# 8x8x8_LED_Cube.net
KiCad netlist of a schematic drawn in Altium Designer
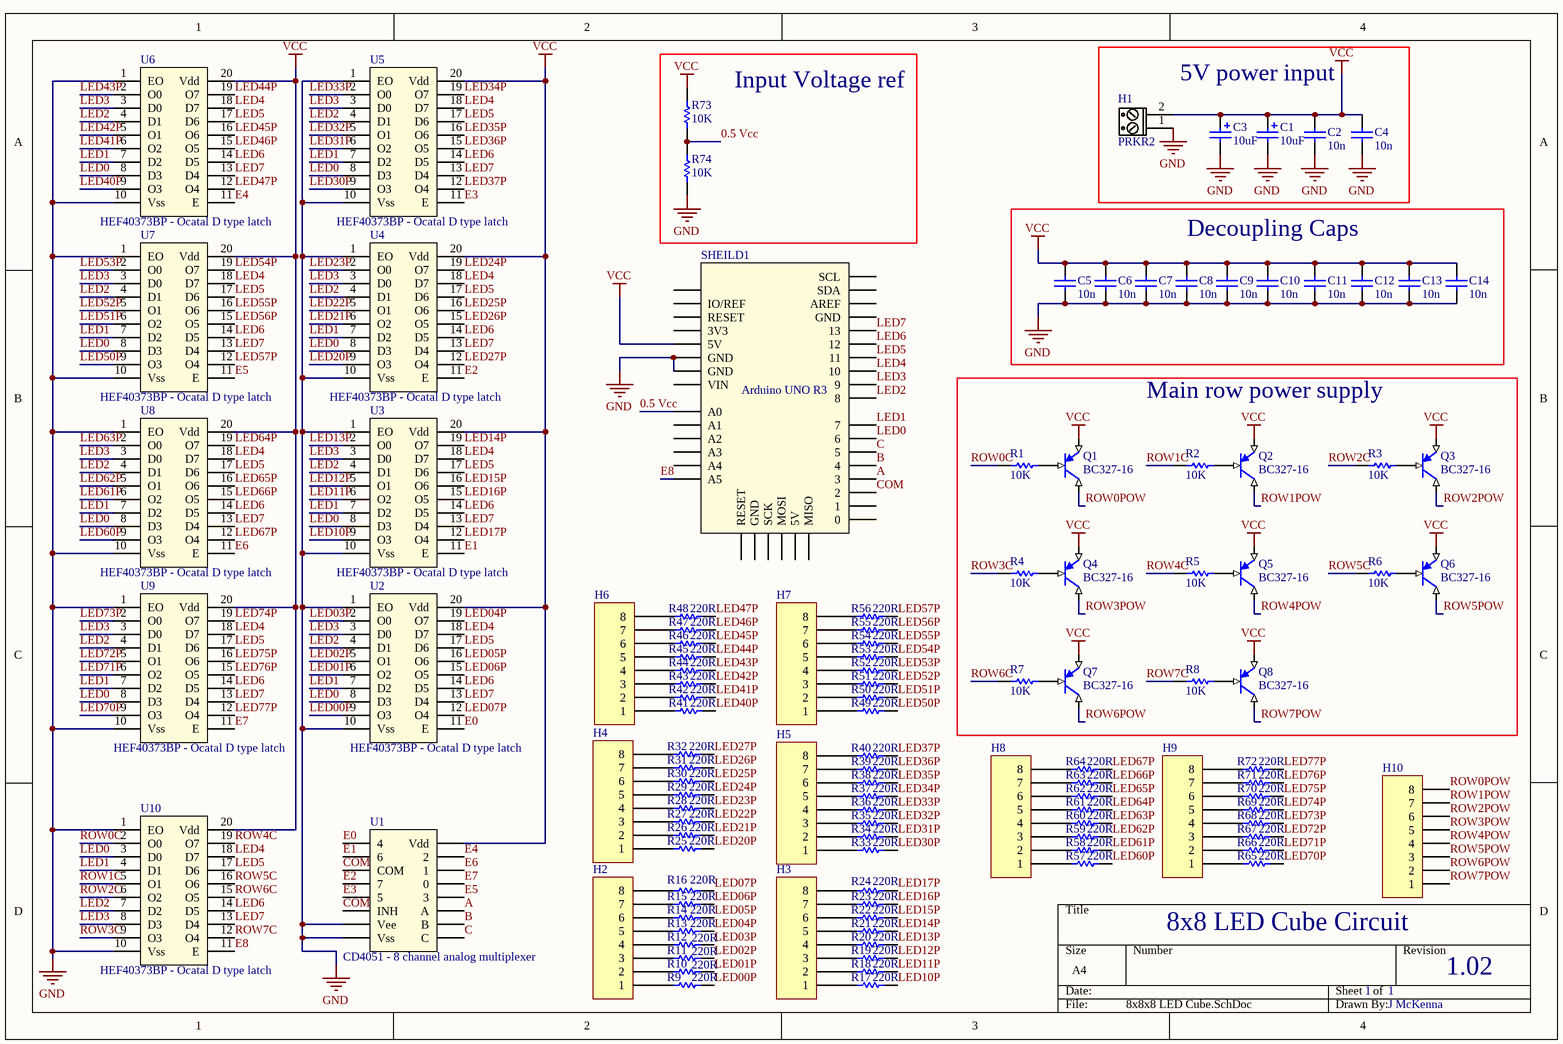
[diagram p0: 8x8x8 LED Cube.SchDoc]

(export (version "E")
  (design (tool "Eeschema 10.0.6"))
  (components
    (comp (ref "C1")
      (value "10uF")
      (footprint "RB.15/.3")
      (description "Polarized Capacitor (Radial)")
      (fields
        (field (name "MANUFACTURER") "Generic Components")
        (field (name "Comment") "Cap Pol1")
        (field (name "PUBLISHER") "Altium Hobart Technology Centre")
      )
      (libsource (lib "MasseyLibs") (part "Cap Pol1"))
    )
    (comp (ref "C2")
      (value "10n")
      (footprint "RAD300")
      (description "Capacitor")
      (fields
        (field (name "MANUFACTURER") "Generic Components")
        (field (name "Comment") "Cap")
        (field (name "PUBLISHER") "Altium Hobart Technology Centre")
      )
      (libsource (lib "MasseyLibs") (part "Cap"))
    )
    (comp (ref "C3")
      (value "10uF")
      (footprint "RB.15/.3")
      (description "Polarized Capacitor (Radial)")
      (fields
        (field (name "MANUFACTURER") "Generic Components")
        (field (name "Comment") "Cap Pol1")
        (field (name "PUBLISHER") "Altium Hobart Technology Centre")
      )
      (libsource (lib "MasseyLibs") (part "Cap Pol1"))
    )
    (comp (ref "C4")
      (value "10n")
      (footprint "RAD300")
      (description "Capacitor")
      (fields
        (field (name "MANUFACTURER") "Generic Components")
        (field (name "Comment") "Cap")
        (field (name "PUBLISHER") "Altium Hobart Technology Centre")
      )
      (libsource (lib "MasseyLibs") (part "Cap"))
    )
    (comp (ref "C5")
      (value "10n")
      (footprint "RAD200_A")
      (description "Capacitor")
      (fields
        (field (name "MANUFACTURER") "Generic Components")
        (field (name "Comment") "Cap")
        (field (name "PUBLISHER") "Altium Hobart Technology Centre")
      )
      (libsource (lib "MasseyLibs") (part "Cap"))
    )
    (comp (ref "C6")
      (value "10n")
      (footprint "RAD200_A")
      (description "Capacitor")
      (fields
        (field (name "MANUFACTURER") "Generic Components")
        (field (name "Comment") "Cap")
        (field (name "PUBLISHER") "Altium Hobart Technology Centre")
      )
      (libsource (lib "MasseyLibs") (part "Cap"))
    )
    (comp (ref "C7")
      (value "10n")
      (footprint "RAD200_A")
      (description "Capacitor")
      (fields
        (field (name "MANUFACTURER") "Generic Components")
        (field (name "Comment") "Cap")
        (field (name "PUBLISHER") "Altium Hobart Technology Centre")
      )
      (libsource (lib "MasseyLibs") (part "Cap"))
    )
    (comp (ref "C8")
      (value "10n")
      (footprint "RAD200_A")
      (description "Capacitor")
      (fields
        (field (name "MANUFACTURER") "Generic Components")
        (field (name "Comment") "Cap")
        (field (name "PUBLISHER") "Altium Hobart Technology Centre")
      )
      (libsource (lib "MasseyLibs") (part "Cap"))
    )
    (comp (ref "C9")
      (value "10n")
      (footprint "RAD200_A")
      (description "Capacitor")
      (fields
        (field (name "MANUFACTURER") "Generic Components")
        (field (name "Comment") "Cap")
        (field (name "PUBLISHER") "Altium Hobart Technology Centre")
      )
      (libsource (lib "MasseyLibs") (part "Cap"))
    )
    (comp (ref "C10")
      (value "10n")
      (footprint "RAD200_A")
      (description "Capacitor")
      (fields
        (field (name "MANUFACTURER") "Generic Components")
        (field (name "Comment") "Cap")
        (field (name "PUBLISHER") "Altium Hobart Technology Centre")
      )
      (libsource (lib "MasseyLibs") (part "Cap"))
    )
    (comp (ref "C11")
      (value "10n")
      (footprint "RAD200_A")
      (description "Capacitor")
      (fields
        (field (name "MANUFACTURER") "Generic Components")
        (field (name "Comment") "Cap")
        (field (name "PUBLISHER") "Altium Hobart Technology Centre")
      )
      (libsource (lib "MasseyLibs") (part "Cap"))
    )
    (comp (ref "C12")
      (value "10n")
      (footprint "RAD200_A")
      (description "Capacitor")
      (fields
        (field (name "MANUFACTURER") "Generic Components")
        (field (name "Comment") "Cap")
        (field (name "PUBLISHER") "Altium Hobart Technology Centre")
      )
      (libsource (lib "MasseyLibs") (part "Cap"))
    )
    (comp (ref "C13")
      (value "10n")
      (footprint "RAD200_A")
      (description "Capacitor")
      (fields
        (field (name "MANUFACTURER") "Generic Components")
        (field (name "Comment") "Cap")
        (field (name "PUBLISHER") "Altium Hobart Technology Centre")
      )
      (libsource (lib "MasseyLibs") (part "Cap"))
    )
    (comp (ref "C14")
      (value "10n")
      (footprint "RAD200_A")
      (description "Capacitor")
      (fields
        (field (name "MANUFACTURER") "Generic Components")
        (field (name "Comment") "Cap")
        (field (name "PUBLISHER") "Altium Hobart Technology Centre")
      )
      (libsource (lib "MasseyLibs") (part "Cap"))
    )
    (comp (ref "H1")
      (value "PRKR2")
      (footprint "PRKR2")
      (description "SCREW TERMINAL 5MM")
      (libsource (lib "vh_altium_library") (part "PRKR2"))
    )
    (comp (ref "H2")
      (value "Header 98")
      (footprint "HDR1X8")
      (description "Header, 8-Pin")
      (fields (field (name "MANUFACTURER") "Generic Components"))
      (libsource (lib "MasseyLibs") (part "Header 8"))
    )
    (comp (ref "H3")
      (value "Header 98")
      (footprint "HDR1X8")
      (description "Header, 8-Pin")
      (fields (field (name "MANUFACTURER") "Generic Components"))
      (libsource (lib "MasseyLibs") (part "Header 8"))
    )
    (comp (ref "H4")
      (value "Header 98")
      (footprint "HDR1X8")
      (description "Header, 8-Pin")
      (fields (field (name "MANUFACTURER") "Generic Components"))
      (libsource (lib "MasseyLibs") (part "Header 8"))
    )
    (comp (ref "H5")
      (value "Header 98")
      (footprint "HDR1X8")
      (description "Header, 8-Pin")
      (fields (field (name "MANUFACTURER") "Generic Components"))
      (libsource (lib "MasseyLibs") (part "Header 8"))
    )
    (comp (ref "H6")
      (value "Header 98")
      (footprint "HDR1X8")
      (description "Header, 8-Pin")
      (fields (field (name "MANUFACTURER") "Generic Components"))
      (libsource (lib "MasseyLibs") (part "Header 8"))
    )
    (comp (ref "H7")
      (value "Header 98")
      (footprint "HDR1X8")
      (description "Header, 8-Pin")
      (fields (field (name "MANUFACTURER") "Generic Components"))
      (libsource (lib "MasseyLibs") (part "Header 8"))
    )
    (comp (ref "H8")
      (value "Header 98")
      (footprint "HDR1X8")
      (description "Header, 8-Pin")
      (fields (field (name "MANUFACTURER") "Generic Components"))
      (libsource (lib "MasseyLibs") (part "Header 8"))
    )
    (comp (ref "H9")
      (value "Header 98")
      (footprint "HDR1X8")
      (description "Header, 8-Pin")
      (fields (field (name "MANUFACTURER") "Generic Components"))
      (libsource (lib "MasseyLibs") (part "Header 8"))
    )
    (comp (ref "H10")
      (value "Header 98")
      (footprint "HDR1X8")
      (description "Header, 8-Pin")
      (fields (field (name "MANUFACTURER") "Generic Components"))
      (libsource (lib "MasseyLibs") (part "Header 8"))
    )
    (comp (ref "Q1")
      (value "BC327-16")
      (footprint "TO-92A")
      (description "PNP BJT")
      (libsource (lib "MasseyLibs") (part "BC327-16"))
    )
    (comp (ref "Q2")
      (value "BC327-16")
      (footprint "TO-92A")
      (description "PNP BJT")
      (libsource (lib "MasseyLibs") (part "BC327-16"))
    )
    (comp (ref "Q3")
      (value "BC327-16")
      (footprint "TO-92A")
      (description "PNP BJT")
      (libsource (lib "MasseyLibs") (part "BC327-16"))
    )
    (comp (ref "Q4")
      (value "BC327-16")
      (footprint "TO-92A")
      (description "PNP BJT")
      (libsource (lib "MasseyLibs") (part "BC327-16"))
    )
    (comp (ref "Q5")
      (value "BC327-16")
      (footprint "TO-92A")
      (description "PNP BJT")
      (libsource (lib "MasseyLibs") (part "BC327-16"))
    )
    (comp (ref "Q6")
      (value "BC327-16")
      (footprint "TO-92A")
      (description "PNP BJT")
      (libsource (lib "MasseyLibs") (part "BC327-16"))
    )
    (comp (ref "Q7")
      (value "BC327-16")
      (footprint "TO-92A")
      (description "PNP BJT")
      (libsource (lib "MasseyLibs") (part "BC327-16"))
    )
    (comp (ref "Q8")
      (value "BC327-16")
      (footprint "TO-92A")
      (description "PNP BJT")
      (libsource (lib "MasseyLibs") (part "BC327-16"))
    )
    (comp (ref "R1")
      (value "10K")
      (footprint "AXIAL400")
      (description "Resistor")
      (fields
        (field (name "MANUFACTURER") "Generic Components")
        (field (name "Comment") "Res1")
        (field (name "PUBLISHER") "Altium Hobart Technology Centre")
      )
      (libsource (lib "MasseyLibs") (part "Res1"))
    )
    (comp (ref "R2")
      (value "10K")
      (footprint "AXIAL400")
      (description "Resistor")
      (fields
        (field (name "MANUFACTURER") "Generic Components")
        (field (name "Comment") "Res1")
        (field (name "PUBLISHER") "Altium Hobart Technology Centre")
      )
      (libsource (lib "MasseyLibs") (part "Res1"))
    )
    (comp (ref "R3")
      (value "10K")
      (footprint "AXIAL400")
      (description "Resistor")
      (fields
        (field (name "MANUFACTURER") "Generic Components")
        (field (name "Comment") "Res1")
        (field (name "PUBLISHER") "Altium Hobart Technology Centre")
      )
      (libsource (lib "MasseyLibs") (part "Res1"))
    )
    (comp (ref "R4")
      (value "10K")
      (footprint "AXIAL400")
      (description "Resistor")
      (fields
        (field (name "MANUFACTURER") "Generic Components")
        (field (name "Comment") "Res1")
        (field (name "PUBLISHER") "Altium Hobart Technology Centre")
      )
      (libsource (lib "MasseyLibs") (part "Res1"))
    )
    (comp (ref "R5")
      (value "10K")
      (footprint "AXIAL400")
      (description "Resistor")
      (fields
        (field (name "MANUFACTURER") "Generic Components")
        (field (name "Comment") "Res1")
        (field (name "PUBLISHER") "Altium Hobart Technology Centre")
      )
      (libsource (lib "MasseyLibs") (part "Res1"))
    )
    (comp (ref "R6")
      (value "10K")
      (footprint "AXIAL400")
      (description "Resistor")
      (fields
        (field (name "MANUFACTURER") "Generic Components")
        (field (name "Comment") "Res1")
        (field (name "PUBLISHER") "Altium Hobart Technology Centre")
      )
      (libsource (lib "MasseyLibs") (part "Res1"))
    )
    (comp (ref "R7")
      (value "10K")
      (footprint "AXIAL400")
      (description "Resistor")
      (fields
        (field (name "MANUFACTURER") "Generic Components")
        (field (name "Comment") "Res1")
        (field (name "PUBLISHER") "Altium Hobart Technology Centre")
      )
      (libsource (lib "MasseyLibs") (part "Res1"))
    )
    (comp (ref "R8")
      (value "10K")
      (footprint "AXIAL400")
      (description "Resistor")
      (fields
        (field (name "MANUFACTURER") "Generic Components")
        (field (name "Comment") "Res1")
        (field (name "PUBLISHER") "Altium Hobart Technology Centre")
      )
      (libsource (lib "MasseyLibs") (part "Res1"))
    )
    (comp (ref "R9")
      (value "220R")
      (footprint "AXIAL400")
      (description "Resistor")
      (fields
        (field (name "MANUFACTURER") "Generic Components")
        (field (name "Comment") "Res1")
        (field (name "PUBLISHER") "Altium Hobart Technology Centre")
      )
      (libsource (lib "MasseyLibs") (part "Res1"))
    )
    (comp (ref "R10")
      (value "220R")
      (footprint "AXIAL400")
      (description "Resistor")
      (fields
        (field (name "MANUFACTURER") "Generic Components")
        (field (name "Comment") "Res1")
        (field (name "PUBLISHER") "Altium Hobart Technology Centre")
      )
      (libsource (lib "MasseyLibs") (part "Res1"))
    )
    (comp (ref "R11")
      (value "220R")
      (footprint "AXIAL400")
      (description "Resistor")
      (fields
        (field (name "MANUFACTURER") "Generic Components")
        (field (name "Comment") "Res1")
        (field (name "PUBLISHER") "Altium Hobart Technology Centre")
      )
      (libsource (lib "MasseyLibs") (part "Res1"))
    )
    (comp (ref "R12")
      (value "220R")
      (footprint "AXIAL400")
      (description "Resistor")
      (fields
        (field (name "MANUFACTURER") "Generic Components")
        (field (name "Comment") "Res1")
        (field (name "PUBLISHER") "Altium Hobart Technology Centre")
      )
      (libsource (lib "MasseyLibs") (part "Res1"))
    )
    (comp (ref "R13")
      (value "220R")
      (footprint "AXIAL400")
      (description "Resistor")
      (fields
        (field (name "MANUFACTURER") "Generic Components")
        (field (name "Comment") "Res1")
        (field (name "PUBLISHER") "Altium Hobart Technology Centre")
      )
      (libsource (lib "MasseyLibs") (part "Res1"))
    )
    (comp (ref "R14")
      (value "220R")
      (footprint "AXIAL400")
      (description "Resistor")
      (fields
        (field (name "MANUFACTURER") "Generic Components")
        (field (name "Comment") "Res1")
        (field (name "PUBLISHER") "Altium Hobart Technology Centre")
      )
      (libsource (lib "MasseyLibs") (part "Res1"))
    )
    (comp (ref "R15")
      (value "220R")
      (footprint "AXIAL400")
      (description "Resistor")
      (fields
        (field (name "MANUFACTURER") "Generic Components")
        (field (name "Comment") "Res1")
        (field (name "PUBLISHER") "Altium Hobart Technology Centre")
      )
      (libsource (lib "MasseyLibs") (part "Res1"))
    )
    (comp (ref "R16")
      (value "220R")
      (footprint "AXIAL400")
      (description "Resistor")
      (fields
        (field (name "MANUFACTURER") "Generic Components")
        (field (name "Comment") "Res1")
        (field (name "PUBLISHER") "Altium Hobart Technology Centre")
      )
      (libsource (lib "MasseyLibs") (part "Res1"))
    )
    (comp (ref "R17")
      (value "220R")
      (footprint "AXIAL400")
      (description "Resistor")
      (fields
        (field (name "MANUFACTURER") "Generic Components")
        (field (name "Comment") "Res1")
        (field (name "PUBLISHER") "Altium Hobart Technology Centre")
      )
      (libsource (lib "MasseyLibs") (part "Res1"))
    )
    (comp (ref "R18")
      (value "220R")
      (footprint "AXIAL400")
      (description "Resistor")
      (fields
        (field (name "MANUFACTURER") "Generic Components")
        (field (name "Comment") "Res1")
        (field (name "PUBLISHER") "Altium Hobart Technology Centre")
      )
      (libsource (lib "MasseyLibs") (part "Res1"))
    )
    (comp (ref "R19")
      (value "220R")
      (footprint "AXIAL400")
      (description "Resistor")
      (fields
        (field (name "MANUFACTURER") "Generic Components")
        (field (name "Comment") "Res1")
        (field (name "PUBLISHER") "Altium Hobart Technology Centre")
      )
      (libsource (lib "MasseyLibs") (part "Res1"))
    )
    (comp (ref "R20")
      (value "220R")
      (footprint "AXIAL400")
      (description "Resistor")
      (fields
        (field (name "MANUFACTURER") "Generic Components")
        (field (name "Comment") "Res1")
        (field (name "PUBLISHER") "Altium Hobart Technology Centre")
      )
      (libsource (lib "MasseyLibs") (part "Res1"))
    )
    (comp (ref "R21")
      (value "220R")
      (footprint "AXIAL400")
      (description "Resistor")
      (fields
        (field (name "MANUFACTURER") "Generic Components")
        (field (name "Comment") "Res1")
        (field (name "PUBLISHER") "Altium Hobart Technology Centre")
      )
      (libsource (lib "MasseyLibs") (part "Res1"))
    )
    (comp (ref "R22")
      (value "220R")
      (footprint "AXIAL400")
      (description "Resistor")
      (fields
        (field (name "MANUFACTURER") "Generic Components")
        (field (name "Comment") "Res1")
        (field (name "PUBLISHER") "Altium Hobart Technology Centre")
      )
      (libsource (lib "MasseyLibs") (part "Res1"))
    )
    (comp (ref "R23")
      (value "220R")
      (footprint "AXIAL400")
      (description "Resistor")
      (fields
        (field (name "MANUFACTURER") "Generic Components")
        (field (name "Comment") "Res1")
        (field (name "PUBLISHER") "Altium Hobart Technology Centre")
      )
      (libsource (lib "MasseyLibs") (part "Res1"))
    )
    (comp (ref "R24")
      (value "220R")
      (footprint "AXIAL400")
      (description "Resistor")
      (fields
        (field (name "MANUFACTURER") "Generic Components")
        (field (name "Comment") "Res1")
        (field (name "PUBLISHER") "Altium Hobart Technology Centre")
      )
      (libsource (lib "MasseyLibs") (part "Res1"))
    )
    (comp (ref "R25")
      (value "220R")
      (footprint "AXIAL400")
      (description "Resistor")
      (fields
        (field (name "MANUFACTURER") "Generic Components")
        (field (name "Comment") "Res1")
        (field (name "PUBLISHER") "Altium Hobart Technology Centre")
      )
      (libsource (lib "MasseyLibs") (part "Res1"))
    )
    (comp (ref "R26")
      (value "220R")
      (footprint "AXIAL400")
      (description "Resistor")
      (fields
        (field (name "MANUFACTURER") "Generic Components")
        (field (name "Comment") "Res1")
        (field (name "PUBLISHER") "Altium Hobart Technology Centre")
      )
      (libsource (lib "MasseyLibs") (part "Res1"))
    )
    (comp (ref "R27")
      (value "220R")
      (footprint "AXIAL400")
      (description "Resistor")
      (fields
        (field (name "MANUFACTURER") "Generic Components")
        (field (name "Comment") "Res1")
        (field (name "PUBLISHER") "Altium Hobart Technology Centre")
      )
      (libsource (lib "MasseyLibs") (part "Res1"))
    )
    (comp (ref "R28")
      (value "220R")
      (footprint "AXIAL400")
      (description "Resistor")
      (fields
        (field (name "MANUFACTURER") "Generic Components")
        (field (name "Comment") "Res1")
        (field (name "PUBLISHER") "Altium Hobart Technology Centre")
      )
      (libsource (lib "MasseyLibs") (part "Res1"))
    )
    (comp (ref "R29")
      (value "220R")
      (footprint "AXIAL400")
      (description "Resistor")
      (fields
        (field (name "MANUFACTURER") "Generic Components")
        (field (name "Comment") "Res1")
        (field (name "PUBLISHER") "Altium Hobart Technology Centre")
      )
      (libsource (lib "MasseyLibs") (part "Res1"))
    )
    (comp (ref "R30")
      (value "220R")
      (footprint "AXIAL400")
      (description "Resistor")
      (fields
        (field (name "MANUFACTURER") "Generic Components")
        (field (name "Comment") "Res1")
        (field (name "PUBLISHER") "Altium Hobart Technology Centre")
      )
      (libsource (lib "MasseyLibs") (part "Res1"))
    )
    (comp (ref "R31")
      (value "220R")
      (footprint "AXIAL400")
      (description "Resistor")
      (fields
        (field (name "MANUFACTURER") "Generic Components")
        (field (name "Comment") "Res1")
        (field (name "PUBLISHER") "Altium Hobart Technology Centre")
      )
      (libsource (lib "MasseyLibs") (part "Res1"))
    )
    (comp (ref "R32")
      (value "220R")
      (footprint "AXIAL400")
      (description "Resistor")
      (fields
        (field (name "MANUFACTURER") "Generic Components")
        (field (name "Comment") "Res1")
        (field (name "PUBLISHER") "Altium Hobart Technology Centre")
      )
      (libsource (lib "MasseyLibs") (part "Res1"))
    )
    (comp (ref "R33")
      (value "220R")
      (footprint "AXIAL400")
      (description "Resistor")
      (fields
        (field (name "MANUFACTURER") "Generic Components")
        (field (name "Comment") "Res1")
        (field (name "PUBLISHER") "Altium Hobart Technology Centre")
      )
      (libsource (lib "MasseyLibs") (part "Res1"))
    )
    (comp (ref "R34")
      (value "220R")
      (footprint "AXIAL400")
      (description "Resistor")
      (fields
        (field (name "MANUFACTURER") "Generic Components")
        (field (name "Comment") "Res1")
        (field (name "PUBLISHER") "Altium Hobart Technology Centre")
      )
      (libsource (lib "MasseyLibs") (part "Res1"))
    )
    (comp (ref "R35")
      (value "220R")
      (footprint "AXIAL400")
      (description "Resistor")
      (fields
        (field (name "MANUFACTURER") "Generic Components")
        (field (name "Comment") "Res1")
        (field (name "PUBLISHER") "Altium Hobart Technology Centre")
      )
      (libsource (lib "MasseyLibs") (part "Res1"))
    )
    (comp (ref "R36")
      (value "220R")
      (footprint "AXIAL400")
      (description "Resistor")
      (fields
        (field (name "MANUFACTURER") "Generic Components")
        (field (name "Comment") "Res1")
        (field (name "PUBLISHER") "Altium Hobart Technology Centre")
      )
      (libsource (lib "MasseyLibs") (part "Res1"))
    )
    (comp (ref "R37")
      (value "220R")
      (footprint "AXIAL400")
      (description "Resistor")
      (fields
        (field (name "MANUFACTURER") "Generic Components")
        (field (name "Comment") "Res1")
        (field (name "PUBLISHER") "Altium Hobart Technology Centre")
      )
      (libsource (lib "MasseyLibs") (part "Res1"))
    )
    (comp (ref "R38")
      (value "220R")
      (footprint "AXIAL400")
      (description "Resistor")
      (fields
        (field (name "MANUFACTURER") "Generic Components")
        (field (name "Comment") "Res1")
        (field (name "PUBLISHER") "Altium Hobart Technology Centre")
      )
      (libsource (lib "MasseyLibs") (part "Res1"))
    )
    (comp (ref "R39")
      (value "220R")
      (footprint "AXIAL400")
      (description "Resistor")
      (fields
        (field (name "MANUFACTURER") "Generic Components")
        (field (name "Comment") "Res1")
        (field (name "PUBLISHER") "Altium Hobart Technology Centre")
      )
      (libsource (lib "MasseyLibs") (part "Res1"))
    )
    (comp (ref "R40")
      (value "220R")
      (footprint "AXIAL400")
      (description "Resistor")
      (fields
        (field (name "MANUFACTURER") "Generic Components")
        (field (name "Comment") "Res1")
        (field (name "PUBLISHER") "Altium Hobart Technology Centre")
      )
      (libsource (lib "MasseyLibs") (part "Res1"))
    )
    (comp (ref "R41")
      (value "220R")
      (footprint "AXIAL400")
      (description "Resistor")
      (fields
        (field (name "MANUFACTURER") "Generic Components")
        (field (name "Comment") "Res1")
        (field (name "PUBLISHER") "Altium Hobart Technology Centre")
      )
      (libsource (lib "MasseyLibs") (part "Res1"))
    )
    (comp (ref "R42")
      (value "220R")
      (footprint "AXIAL400")
      (description "Resistor")
      (fields
        (field (name "MANUFACTURER") "Generic Components")
        (field (name "Comment") "Res1")
        (field (name "PUBLISHER") "Altium Hobart Technology Centre")
      )
      (libsource (lib "MasseyLibs") (part "Res1"))
    )
    (comp (ref "R43")
      (value "220R")
      (footprint "AXIAL400")
      (description "Resistor")
      (fields
        (field (name "MANUFACTURER") "Generic Components")
        (field (name "Comment") "Res1")
        (field (name "PUBLISHER") "Altium Hobart Technology Centre")
      )
      (libsource (lib "MasseyLibs") (part "Res1"))
    )
    (comp (ref "R44")
      (value "220R")
      (footprint "AXIAL400")
      (description "Resistor")
      (fields
        (field (name "MANUFACTURER") "Generic Components")
        (field (name "Comment") "Res1")
        (field (name "PUBLISHER") "Altium Hobart Technology Centre")
      )
      (libsource (lib "MasseyLibs") (part "Res1"))
    )
    (comp (ref "R45")
      (value "220R")
      (footprint "AXIAL400")
      (description "Resistor")
      (fields
        (field (name "MANUFACTURER") "Generic Components")
        (field (name "Comment") "Res1")
        (field (name "PUBLISHER") "Altium Hobart Technology Centre")
      )
      (libsource (lib "MasseyLibs") (part "Res1"))
    )
    (comp (ref "R46")
      (value "220R")
      (footprint "AXIAL400")
      (description "Resistor")
      (fields
        (field (name "MANUFACTURER") "Generic Components")
        (field (name "Comment") "Res1")
        (field (name "PUBLISHER") "Altium Hobart Technology Centre")
      )
      (libsource (lib "MasseyLibs") (part "Res1"))
    )
    (comp (ref "R47")
      (value "220R")
      (footprint "AXIAL400")
      (description "Resistor")
      (fields
        (field (name "MANUFACTURER") "Generic Components")
        (field (name "Comment") "Res1")
        (field (name "PUBLISHER") "Altium Hobart Technology Centre")
      )
      (libsource (lib "MasseyLibs") (part "Res1"))
    )
    (comp (ref "R48")
      (value "220R")
      (footprint "AXIAL400")
      (description "Resistor")
      (fields
        (field (name "MANUFACTURER") "Generic Components")
        (field (name "Comment") "Res1")
        (field (name "PUBLISHER") "Altium Hobart Technology Centre")
      )
      (libsource (lib "MasseyLibs") (part "Res1"))
    )
    (comp (ref "R49")
      (value "220R")
      (footprint "AXIAL400")
      (description "Resistor")
      (fields
        (field (name "MANUFACTURER") "Generic Components")
        (field (name "Comment") "Res1")
        (field (name "PUBLISHER") "Altium Hobart Technology Centre")
      )
      (libsource (lib "MasseyLibs") (part "Res1"))
    )
    (comp (ref "R50")
      (value "220R")
      (footprint "AXIAL400")
      (description "Resistor")
      (fields
        (field (name "MANUFACTURER") "Generic Components")
        (field (name "Comment") "Res1")
        (field (name "PUBLISHER") "Altium Hobart Technology Centre")
      )
      (libsource (lib "MasseyLibs") (part "Res1"))
    )
    (comp (ref "R51")
      (value "220R")
      (footprint "AXIAL400")
      (description "Resistor")
      (fields
        (field (name "MANUFACTURER") "Generic Components")
        (field (name "Comment") "Res1")
        (field (name "PUBLISHER") "Altium Hobart Technology Centre")
      )
      (libsource (lib "MasseyLibs") (part "Res1"))
    )
    (comp (ref "R52")
      (value "220R")
      (footprint "AXIAL400")
      (description "Resistor")
      (fields
        (field (name "MANUFACTURER") "Generic Components")
        (field (name "Comment") "Res1")
        (field (name "PUBLISHER") "Altium Hobart Technology Centre")
      )
      (libsource (lib "MasseyLibs") (part "Res1"))
    )
    (comp (ref "R53")
      (value "220R")
      (footprint "AXIAL400")
      (description "Resistor")
      (fields
        (field (name "MANUFACTURER") "Generic Components")
        (field (name "Comment") "Res1")
        (field (name "PUBLISHER") "Altium Hobart Technology Centre")
      )
      (libsource (lib "MasseyLibs") (part "Res1"))
    )
    (comp (ref "R54")
      (value "220R")
      (footprint "AXIAL400")
      (description "Resistor")
      (fields
        (field (name "MANUFACTURER") "Generic Components")
        (field (name "Comment") "Res1")
        (field (name "PUBLISHER") "Altium Hobart Technology Centre")
      )
      (libsource (lib "MasseyLibs") (part "Res1"))
    )
    (comp (ref "R55")
      (value "220R")
      (footprint "AXIAL400")
      (description "Resistor")
      (fields
        (field (name "MANUFACTURER") "Generic Components")
        (field (name "Comment") "Res1")
        (field (name "PUBLISHER") "Altium Hobart Technology Centre")
      )
      (libsource (lib "MasseyLibs") (part "Res1"))
    )
    (comp (ref "R56")
      (value "220R")
      (footprint "AXIAL400")
      (description "Resistor")
      (fields
        (field (name "MANUFACTURER") "Generic Components")
        (field (name "Comment") "Res1")
        (field (name "PUBLISHER") "Altium Hobart Technology Centre")
      )
      (libsource (lib "MasseyLibs") (part "Res1"))
    )
    (comp (ref "R57")
      (value "220R")
      (footprint "AXIAL400")
      (description "Resistor")
      (fields
        (field (name "MANUFACTURER") "Generic Components")
        (field (name "Comment") "Res1")
        (field (name "PUBLISHER") "Altium Hobart Technology Centre")
      )
      (libsource (lib "MasseyLibs") (part "Res1"))
    )
    (comp (ref "R58")
      (value "220R")
      (footprint "AXIAL400")
      (description "Resistor")
      (fields
        (field (name "MANUFACTURER") "Generic Components")
        (field (name "Comment") "Res1")
        (field (name "PUBLISHER") "Altium Hobart Technology Centre")
      )
      (libsource (lib "MasseyLibs") (part "Res1"))
    )
    (comp (ref "R59")
      (value "220R")
      (footprint "AXIAL400")
      (description "Resistor")
      (fields
        (field (name "MANUFACTURER") "Generic Components")
        (field (name "Comment") "Res1")
        (field (name "PUBLISHER") "Altium Hobart Technology Centre")
      )
      (libsource (lib "MasseyLibs") (part "Res1"))
    )
    (comp (ref "R60")
      (value "220R")
      (footprint "AXIAL400")
      (description "Resistor")
      (fields
        (field (name "MANUFACTURER") "Generic Components")
        (field (name "Comment") "Res1")
        (field (name "PUBLISHER") "Altium Hobart Technology Centre")
      )
      (libsource (lib "MasseyLibs") (part "Res1"))
    )
    (comp (ref "R61")
      (value "220R")
      (footprint "AXIAL400")
      (description "Resistor")
      (fields
        (field (name "MANUFACTURER") "Generic Components")
        (field (name "Comment") "Res1")
        (field (name "PUBLISHER") "Altium Hobart Technology Centre")
      )
      (libsource (lib "MasseyLibs") (part "Res1"))
    )
    (comp (ref "R62")
      (value "220R")
      (footprint "AXIAL400")
      (description "Resistor")
      (fields
        (field (name "MANUFACTURER") "Generic Components")
        (field (name "Comment") "Res1")
        (field (name "PUBLISHER") "Altium Hobart Technology Centre")
      )
      (libsource (lib "MasseyLibs") (part "Res1"))
    )
    (comp (ref "R63")
      (value "220R")
      (footprint "AXIAL400")
      (description "Resistor")
      (fields
        (field (name "MANUFACTURER") "Generic Components")
        (field (name "Comment") "Res1")
        (field (name "PUBLISHER") "Altium Hobart Technology Centre")
      )
      (libsource (lib "MasseyLibs") (part "Res1"))
    )
    (comp (ref "R64")
      (value "220R")
      (footprint "AXIAL400")
      (description "Resistor")
      (fields
        (field (name "MANUFACTURER") "Generic Components")
        (field (name "Comment") "Res1")
        (field (name "PUBLISHER") "Altium Hobart Technology Centre")
      )
      (libsource (lib "MasseyLibs") (part "Res1"))
    )
    (comp (ref "R65")
      (value "220R")
      (footprint "AXIAL400")
      (description "Resistor")
      (fields
        (field (name "MANUFACTURER") "Generic Components")
        (field (name "Comment") "Res1")
        (field (name "PUBLISHER") "Altium Hobart Technology Centre")
      )
      (libsource (lib "MasseyLibs") (part "Res1"))
    )
    (comp (ref "R66")
      (value "220R")
      (footprint "AXIAL400")
      (description "Resistor")
      (fields
        (field (name "MANUFACTURER") "Generic Components")
        (field (name "Comment") "Res1")
        (field (name "PUBLISHER") "Altium Hobart Technology Centre")
      )
      (libsource (lib "MasseyLibs") (part "Res1"))
    )
    (comp (ref "R67")
      (value "220R")
      (footprint "AXIAL400")
      (description "Resistor")
      (fields
        (field (name "MANUFACTURER") "Generic Components")
        (field (name "Comment") "Res1")
        (field (name "PUBLISHER") "Altium Hobart Technology Centre")
      )
      (libsource (lib "MasseyLibs") (part "Res1"))
    )
    (comp (ref "R68")
      (value "220R")
      (footprint "AXIAL400")
      (description "Resistor")
      (fields
        (field (name "MANUFACTURER") "Generic Components")
        (field (name "Comment") "Res1")
        (field (name "PUBLISHER") "Altium Hobart Technology Centre")
      )
      (libsource (lib "MasseyLibs") (part "Res1"))
    )
    (comp (ref "R69")
      (value "220R")
      (footprint "AXIAL400")
      (description "Resistor")
      (fields
        (field (name "MANUFACTURER") "Generic Components")
        (field (name "Comment") "Res1")
        (field (name "PUBLISHER") "Altium Hobart Technology Centre")
      )
      (libsource (lib "MasseyLibs") (part "Res1"))
    )
    (comp (ref "R70")
      (value "220R")
      (footprint "AXIAL400")
      (description "Resistor")
      (fields
        (field (name "MANUFACTURER") "Generic Components")
        (field (name "Comment") "Res1")
        (field (name "PUBLISHER") "Altium Hobart Technology Centre")
      )
      (libsource (lib "MasseyLibs") (part "Res1"))
    )
    (comp (ref "R71")
      (value "220R")
      (footprint "AXIAL400")
      (description "Resistor")
      (fields
        (field (name "MANUFACTURER") "Generic Components")
        (field (name "Comment") "Res1")
        (field (name "PUBLISHER") "Altium Hobart Technology Centre")
      )
      (libsource (lib "MasseyLibs") (part "Res1"))
    )
    (comp (ref "R72")
      (value "220R")
      (footprint "AXIAL400")
      (description "Resistor")
      (fields
        (field (name "MANUFACTURER") "Generic Components")
        (field (name "Comment") "Res1")
        (field (name "PUBLISHER") "Altium Hobart Technology Centre")
      )
      (libsource (lib "MasseyLibs") (part "Res1"))
    )
    (comp (ref "R73")
      (value "10K")
      (footprint "AXIAL400")
      (description "Resistor")
      (fields
        (field (name "MANUFACTURER") "Generic Components")
        (field (name "Comment") "Res1")
        (field (name "PUBLISHER") "Altium Hobart Technology Centre")
      )
      (libsource (lib "MasseyLibs") (part "Res1"))
    )
    (comp (ref "R74")
      (value "10K")
      (footprint "AXIAL400")
      (description "Resistor")
      (fields
        (field (name "MANUFACTURER") "Generic Components")
        (field (name "Comment") "Res1")
        (field (name "PUBLISHER") "Altium Hobart Technology Centre")
      )
      (libsource (lib "MasseyLibs") (part "Res1"))
    )
    (comp (ref "SHEILD1")
      (value "Arduino UNO sheild")
      (footprint "Arduino UNO R3")
      (libsource (lib "vh_altium_library") (part "Arduino UNO sheild"))
    )
    (comp (ref "U1")
      (value "CD4051 - 8 channel analog multiplexer")
      (footprint "DIP16")
      (libsource (lib "vh_altium_library") (part "CD4051 - 8 channel analog multiplexer"))
    )
    (comp (ref "U2")
      (value "HEF40373BP - Ocatal D type latch")
      (footprint "DIP20")
      (libsource (lib "vh_altium_library") (part "HEF40373BP - Ocatal D type latch"))
    )
    (comp (ref "U3")
      (value "HEF40373BP - Ocatal D type latch")
      (footprint "DIP20")
      (libsource (lib "vh_altium_library") (part "HEF40373BP - Ocatal D type latch"))
    )
    (comp (ref "U4")
      (value "HEF40373BP - Ocatal D type latch")
      (footprint "DIP20")
      (libsource (lib "vh_altium_library") (part "HEF40373BP - Ocatal D type latch"))
    )
    (comp (ref "U5")
      (value "HEF40373BP - Ocatal D type latch")
      (footprint "DIP20")
      (libsource (lib "vh_altium_library") (part "HEF40373BP - Ocatal D type latch"))
    )
    (comp (ref "U6")
      (value "HEF40373BP - Ocatal D type latch")
      (footprint "DIP20")
      (libsource (lib "vh_altium_library") (part "HEF40373BP - Ocatal D type latch"))
    )
    (comp (ref "U7")
      (value "HEF40373BP - Ocatal D type latch")
      (footprint "DIP20")
      (libsource (lib "vh_altium_library") (part "HEF40373BP - Ocatal D type latch"))
    )
    (comp (ref "U8")
      (value "HEF40373BP - Ocatal D type latch")
      (footprint "DIP20")
      (libsource (lib "vh_altium_library") (part "HEF40373BP - Ocatal D type latch"))
    )
    (comp (ref "U9")
      (value "HEF40373BP - Ocatal D type latch")
      (footprint "DIP20")
      (libsource (lib "vh_altium_library") (part "HEF40373BP - Ocatal D type latch"))
    )
    (comp (ref "U10")
      (value "HEF40373BP - Ocatal D type latch")
      (footprint "DIP20")
      (libsource (lib "vh_altium_library") (part "HEF40373BP - Ocatal D type latch"))
    )
  )
  (nets
    (net (code "1") (name "/0.5 Vcc") (class "Default")
      (node (ref "R73") (pin "1") (pinfunction "1_1") (pintype "passive"))
      (node (ref "R74") (pin "2") (pinfunction "2_2") (pintype "passive"))
      (node (ref "SHEILD1") (pin "9") (pinfunction "A0_9") (pintype "passive"))
    )
    (net (code "2") (name "/A") (class "Default")
      (node (ref "SHEILD1") (pin "18") (pinfunction "3_18") (pintype "passive"))
      (node (ref "U1") (pin "11") (pinfunction "A_11") (pintype "passive"))
    )
    (net (code "3") (name "/B") (class "Default")
      (node (ref "SHEILD1") (pin "19") (pinfunction "4_19") (pintype "passive"))
      (node (ref "U1") (pin "10") (pinfunction "B_10") (pintype "passive"))
    )
    (net (code "4") (name "/C") (class "Default")
      (node (ref "SHEILD1") (pin "20") (pinfunction "5_20") (pintype "passive"))
      (node (ref "U1") (pin "9") (pinfunction "C_9") (pintype "passive"))
    )
    (net (code "5") (name "/COM") (class "Default")
      (node (ref "SHEILD1") (pin "17") (pinfunction "2_17") (pintype "passive"))
      (node (ref "U1") (pin "3") (pinfunction "COM_3") (pintype "passive"))
      (node (ref "U1") (pin "6") (pinfunction "INH_6") (pintype "passive"))
    )
    (net (code "6") (name "/E0") (class "Default")
      (node (ref "U1") (pin "1") (pinfunction "4_1") (pintype "passive"))
      (node (ref "U2") (pin "11") (pinfunction "E_11") (pintype "passive"))
    )
    (net (code "7") (name "/E1") (class "Default")
      (node (ref "U1") (pin "2") (pinfunction "6_2") (pintype "passive"))
      (node (ref "U3") (pin "11") (pinfunction "E_11") (pintype "passive"))
    )
    (net (code "8") (name "/E2") (class "Default")
      (node (ref "U1") (pin "4") (pinfunction "7_4") (pintype "passive"))
      (node (ref "U4") (pin "11") (pinfunction "E_11") (pintype "passive"))
    )
    (net (code "9") (name "/E3") (class "Default")
      (node (ref "U1") (pin "5") (pinfunction "5_5") (pintype "passive"))
      (node (ref "U5") (pin "11") (pinfunction "E_11") (pintype "passive"))
    )
    (net (code "10") (name "/E4") (class "Default")
      (node (ref "U1") (pin "15") (pinfunction "2_15") (pintype "passive"))
      (node (ref "U6") (pin "11") (pinfunction "E_11") (pintype "passive"))
    )
    (net (code "11") (name "/E5") (class "Default")
      (node (ref "U1") (pin "12") (pinfunction "3_12") (pintype "passive"))
      (node (ref "U7") (pin "11") (pinfunction "E_11") (pintype "passive"))
    )
    (net (code "12") (name "/E6") (class "Default")
      (node (ref "U1") (pin "14") (pinfunction "1_14") (pintype "passive"))
      (node (ref "U8") (pin "11") (pinfunction "E_11") (pintype "passive"))
    )
    (net (code "13") (name "/E7") (class "Default")
      (node (ref "U1") (pin "13") (pinfunction "0_13") (pintype "passive"))
      (node (ref "U9") (pin "11") (pinfunction "E_11") (pintype "passive"))
    )
    (net (code "14") (name "/E8") (class "Default")
      (node (ref "SHEILD1") (pin "14") (pinfunction "A5_14") (pintype "passive"))
      (node (ref "U10") (pin "11") (pinfunction "E_11") (pintype "passive"))
    )
    (net (code "15") (name "/LED0") (class "Default")
      (node (ref "SHEILD1") (pin "21") (pinfunction "6_21") (pintype "passive"))
      (node (ref "U10") (pin "3") (pinfunction "D0_3") (pintype "passive"))
      (node (ref "U2") (pin "8") (pinfunction "D3_8") (pintype "passive"))
      (node (ref "U3") (pin "8") (pinfunction "D3_8") (pintype "passive"))
      (node (ref "U4") (pin "8") (pinfunction "D3_8") (pintype "passive"))
      (node (ref "U5") (pin "8") (pinfunction "D3_8") (pintype "passive"))
      (node (ref "U6") (pin "8") (pinfunction "D3_8") (pintype "passive"))
      (node (ref "U7") (pin "8") (pinfunction "D3_8") (pintype "passive"))
      (node (ref "U8") (pin "8") (pinfunction "D3_8") (pintype "passive"))
      (node (ref "U9") (pin "8") (pinfunction "D3_8") (pintype "passive"))
    )
    (net (code "16") (name "/LED00P") (class "Default")
      (node (ref "R9") (pin "2") (pinfunction "2_2") (pintype "passive"))
      (node (ref "U2") (pin "9") (pinfunction "O3_9") (pintype "passive"))
    )
    (net (code "17") (name "/LED1") (class "Default")
      (node (ref "SHEILD1") (pin "22") (pinfunction "7_22") (pintype "passive"))
      (node (ref "U10") (pin "4") (pinfunction "D1_4") (pintype "passive"))
      (node (ref "U2") (pin "7") (pinfunction "D2_7") (pintype "passive"))
      (node (ref "U3") (pin "7") (pinfunction "D2_7") (pintype "passive"))
      (node (ref "U4") (pin "7") (pinfunction "D2_7") (pintype "passive"))
      (node (ref "U5") (pin "7") (pinfunction "D2_7") (pintype "passive"))
      (node (ref "U6") (pin "7") (pinfunction "D2_7") (pintype "passive"))
      (node (ref "U7") (pin "7") (pinfunction "D2_7") (pintype "passive"))
      (node (ref "U8") (pin "7") (pinfunction "D2_7") (pintype "passive"))
      (node (ref "U9") (pin "7") (pinfunction "D2_7") (pintype "passive"))
    )
    (net (code "18") (name "/LED01P") (class "Default")
      (node (ref "R10") (pin "2") (pinfunction "2_2") (pintype "passive"))
      (node (ref "U2") (pin "6") (pinfunction "O2_6") (pintype "passive"))
    )
    (net (code "19") (name "/LED2") (class "Default")
      (node (ref "SHEILD1") (pin "23") (pinfunction "8_23") (pintype "passive"))
      (node (ref "U10") (pin "7") (pinfunction "D2_7") (pintype "passive"))
      (node (ref "U2") (pin "4") (pinfunction "D1_4") (pintype "passive"))
      (node (ref "U3") (pin "4") (pinfunction "D1_4") (pintype "passive"))
      (node (ref "U4") (pin "4") (pinfunction "D1_4") (pintype "passive"))
      (node (ref "U5") (pin "4") (pinfunction "D1_4") (pintype "passive"))
      (node (ref "U6") (pin "4") (pinfunction "D1_4") (pintype "passive"))
      (node (ref "U7") (pin "4") (pinfunction "D1_4") (pintype "passive"))
      (node (ref "U8") (pin "4") (pinfunction "D1_4") (pintype "passive"))
      (node (ref "U9") (pin "4") (pinfunction "D1_4") (pintype "passive"))
    )
    (net (code "20") (name "/LED02P") (class "Default")
      (node (ref "R11") (pin "2") (pinfunction "2_2") (pintype "passive"))
      (node (ref "U2") (pin "5") (pinfunction "O1_5") (pintype "passive"))
    )
    (net (code "21") (name "/LED3") (class "Default")
      (node (ref "SHEILD1") (pin "24") (pinfunction "9_24") (pintype "passive"))
      (node (ref "U10") (pin "8") (pinfunction "D3_8") (pintype "passive"))
      (node (ref "U2") (pin "3") (pinfunction "D0_3") (pintype "passive"))
      (node (ref "U3") (pin "3") (pinfunction "D0_3") (pintype "passive"))
      (node (ref "U4") (pin "3") (pinfunction "D0_3") (pintype "passive"))
      (node (ref "U5") (pin "3") (pinfunction "D0_3") (pintype "passive"))
      (node (ref "U6") (pin "3") (pinfunction "D0_3") (pintype "passive"))
      (node (ref "U7") (pin "3") (pinfunction "D0_3") (pintype "passive"))
      (node (ref "U8") (pin "3") (pinfunction "D0_3") (pintype "passive"))
      (node (ref "U9") (pin "3") (pinfunction "D0_3") (pintype "passive"))
    )
    (net (code "22") (name "/LED03P") (class "Default")
      (node (ref "R12") (pin "2") (pinfunction "2_2") (pintype "passive"))
      (node (ref "U2") (pin "2") (pinfunction "O0_2") (pintype "passive"))
    )
    (net (code "23") (name "/LED4") (class "Default")
      (node (ref "SHEILD1") (pin "25") (pinfunction "10_25") (pintype "passive"))
      (node (ref "U10") (pin "18") (pinfunction "D7_18") (pintype "passive"))
      (node (ref "U2") (pin "18") (pinfunction "D7_18") (pintype "passive"))
      (node (ref "U3") (pin "18") (pinfunction "D7_18") (pintype "passive"))
      (node (ref "U4") (pin "18") (pinfunction "D7_18") (pintype "passive"))
      (node (ref "U5") (pin "18") (pinfunction "D7_18") (pintype "passive"))
      (node (ref "U6") (pin "18") (pinfunction "D7_18") (pintype "passive"))
      (node (ref "U7") (pin "18") (pinfunction "D7_18") (pintype "passive"))
      (node (ref "U8") (pin "18") (pinfunction "D7_18") (pintype "passive"))
      (node (ref "U9") (pin "18") (pinfunction "D7_18") (pintype "passive"))
    )
    (net (code "24") (name "/LED04P") (class "Default")
      (node (ref "R13") (pin "2") (pinfunction "2_2") (pintype "passive"))
      (node (ref "U2") (pin "19") (pinfunction "O7_19") (pintype "passive"))
    )
    (net (code "25") (name "/LED5") (class "Default")
      (node (ref "SHEILD1") (pin "26") (pinfunction "11_26") (pintype "passive"))
      (node (ref "U10") (pin "17") (pinfunction "D6_17") (pintype "passive"))
      (node (ref "U2") (pin "17") (pinfunction "D6_17") (pintype "passive"))
      (node (ref "U3") (pin "17") (pinfunction "D6_17") (pintype "passive"))
      (node (ref "U4") (pin "17") (pinfunction "D6_17") (pintype "passive"))
      (node (ref "U5") (pin "17") (pinfunction "D6_17") (pintype "passive"))
      (node (ref "U6") (pin "17") (pinfunction "D6_17") (pintype "passive"))
      (node (ref "U7") (pin "17") (pinfunction "D6_17") (pintype "passive"))
      (node (ref "U8") (pin "17") (pinfunction "D6_17") (pintype "passive"))
      (node (ref "U9") (pin "17") (pinfunction "D6_17") (pintype "passive"))
    )
    (net (code "26") (name "/LED05P") (class "Default")
      (node (ref "R14") (pin "2") (pinfunction "2_2") (pintype "passive"))
      (node (ref "U2") (pin "16") (pinfunction "O6_16") (pintype "passive"))
    )
    (net (code "27") (name "/LED6") (class "Default")
      (node (ref "SHEILD1") (pin "27") (pinfunction "12_27") (pintype "passive"))
      (node (ref "U10") (pin "14") (pinfunction "D5_14") (pintype "passive"))
      (node (ref "U2") (pin "14") (pinfunction "D5_14") (pintype "passive"))
      (node (ref "U3") (pin "14") (pinfunction "D5_14") (pintype "passive"))
      (node (ref "U4") (pin "14") (pinfunction "D5_14") (pintype "passive"))
      (node (ref "U5") (pin "14") (pinfunction "D5_14") (pintype "passive"))
      (node (ref "U6") (pin "14") (pinfunction "D5_14") (pintype "passive"))
      (node (ref "U7") (pin "14") (pinfunction "D5_14") (pintype "passive"))
      (node (ref "U8") (pin "14") (pinfunction "D5_14") (pintype "passive"))
      (node (ref "U9") (pin "14") (pinfunction "D5_14") (pintype "passive"))
    )
    (net (code "28") (name "/LED06P") (class "Default")
      (node (ref "R15") (pin "2") (pinfunction "2_2") (pintype "passive"))
      (node (ref "U2") (pin "15") (pinfunction "O5_15") (pintype "passive"))
    )
    (net (code "29") (name "/LED7") (class "Default")
      (node (ref "SHEILD1") (pin "28") (pinfunction "13_28") (pintype "passive"))
      (node (ref "U10") (pin "13") (pinfunction "D4_13") (pintype "passive"))
      (node (ref "U2") (pin "13") (pinfunction "D4_13") (pintype "passive"))
      (node (ref "U3") (pin "13") (pinfunction "D4_13") (pintype "passive"))
      (node (ref "U4") (pin "13") (pinfunction "D4_13") (pintype "passive"))
      (node (ref "U5") (pin "13") (pinfunction "D4_13") (pintype "passive"))
      (node (ref "U6") (pin "13") (pinfunction "D4_13") (pintype "passive"))
      (node (ref "U7") (pin "13") (pinfunction "D4_13") (pintype "passive"))
      (node (ref "U8") (pin "13") (pinfunction "D4_13") (pintype "passive"))
      (node (ref "U9") (pin "13") (pinfunction "D4_13") (pintype "passive"))
    )
    (net (code "30") (name "/LED07P") (class "Default")
      (node (ref "R16") (pin "2") (pinfunction "2_2") (pintype "passive"))
      (node (ref "U2") (pin "12") (pinfunction "O4_12") (pintype "passive"))
    )
    (net (code "31") (name "/LED10P") (class "Default")
      (node (ref "R17") (pin "2") (pinfunction "2_2") (pintype "passive"))
      (node (ref "U3") (pin "9") (pinfunction "O3_9") (pintype "passive"))
    )
    (net (code "32") (name "/LED11P") (class "Default")
      (node (ref "R18") (pin "2") (pinfunction "2_2") (pintype "passive"))
      (node (ref "U3") (pin "6") (pinfunction "O2_6") (pintype "passive"))
    )
    (net (code "33") (name "/LED12P") (class "Default")
      (node (ref "R19") (pin "2") (pinfunction "2_2") (pintype "passive"))
      (node (ref "U3") (pin "5") (pinfunction "O1_5") (pintype "passive"))
    )
    (net (code "34") (name "/LED13P") (class "Default")
      (node (ref "R20") (pin "2") (pinfunction "2_2") (pintype "passive"))
      (node (ref "U3") (pin "2") (pinfunction "O0_2") (pintype "passive"))
    )
    (net (code "35") (name "/LED14P") (class "Default")
      (node (ref "R21") (pin "2") (pinfunction "2_2") (pintype "passive"))
      (node (ref "U3") (pin "19") (pinfunction "O7_19") (pintype "passive"))
    )
    (net (code "36") (name "/LED15P") (class "Default")
      (node (ref "R22") (pin "2") (pinfunction "2_2") (pintype "passive"))
      (node (ref "U3") (pin "16") (pinfunction "O6_16") (pintype "passive"))
    )
    (net (code "37") (name "/LED16P") (class "Default")
      (node (ref "R23") (pin "2") (pinfunction "2_2") (pintype "passive"))
      (node (ref "U3") (pin "15") (pinfunction "O5_15") (pintype "passive"))
    )
    (net (code "38") (name "/LED17P") (class "Default")
      (node (ref "R24") (pin "2") (pinfunction "2_2") (pintype "passive"))
      (node (ref "U3") (pin "12") (pinfunction "O4_12") (pintype "passive"))
    )
    (net (code "39") (name "/LED20P") (class "Default")
      (node (ref "R25") (pin "2") (pinfunction "2_2") (pintype "passive"))
      (node (ref "U4") (pin "9") (pinfunction "O3_9") (pintype "passive"))
    )
    (net (code "40") (name "/LED21P") (class "Default")
      (node (ref "R26") (pin "2") (pinfunction "2_2") (pintype "passive"))
      (node (ref "U4") (pin "6") (pinfunction "O2_6") (pintype "passive"))
    )
    (net (code "41") (name "/LED22P") (class "Default")
      (node (ref "R27") (pin "2") (pinfunction "2_2") (pintype "passive"))
      (node (ref "U4") (pin "5") (pinfunction "O1_5") (pintype "passive"))
    )
    (net (code "42") (name "/LED23P") (class "Default")
      (node (ref "R28") (pin "2") (pinfunction "2_2") (pintype "passive"))
      (node (ref "U4") (pin "2") (pinfunction "O0_2") (pintype "passive"))
    )
    (net (code "43") (name "/LED24P") (class "Default")
      (node (ref "R29") (pin "2") (pinfunction "2_2") (pintype "passive"))
      (node (ref "U4") (pin "19") (pinfunction "O7_19") (pintype "passive"))
    )
    (net (code "44") (name "/LED25P") (class "Default")
      (node (ref "R30") (pin "2") (pinfunction "2_2") (pintype "passive"))
      (node (ref "U4") (pin "16") (pinfunction "O6_16") (pintype "passive"))
    )
    (net (code "45") (name "/LED26P") (class "Default")
      (node (ref "R31") (pin "2") (pinfunction "2_2") (pintype "passive"))
      (node (ref "U4") (pin "15") (pinfunction "O5_15") (pintype "passive"))
    )
    (net (code "46") (name "/LED27P") (class "Default")
      (node (ref "R32") (pin "2") (pinfunction "2_2") (pintype "passive"))
      (node (ref "U4") (pin "12") (pinfunction "O4_12") (pintype "passive"))
    )
    (net (code "47") (name "/LED30P") (class "Default")
      (node (ref "R33") (pin "2") (pinfunction "2_2") (pintype "passive"))
      (node (ref "U5") (pin "9") (pinfunction "O3_9") (pintype "passive"))
    )
    (net (code "48") (name "/LED31P") (class "Default")
      (node (ref "R34") (pin "2") (pinfunction "2_2") (pintype "passive"))
      (node (ref "U5") (pin "6") (pinfunction "O2_6") (pintype "passive"))
    )
    (net (code "49") (name "/LED32P") (class "Default")
      (node (ref "R35") (pin "2") (pinfunction "2_2") (pintype "passive"))
      (node (ref "U5") (pin "5") (pinfunction "O1_5") (pintype "passive"))
    )
    (net (code "50") (name "/LED33P") (class "Default")
      (node (ref "R36") (pin "2") (pinfunction "2_2") (pintype "passive"))
      (node (ref "U5") (pin "2") (pinfunction "O0_2") (pintype "passive"))
    )
    (net (code "51") (name "/LED34P") (class "Default")
      (node (ref "R37") (pin "2") (pinfunction "2_2") (pintype "passive"))
      (node (ref "U5") (pin "19") (pinfunction "O7_19") (pintype "passive"))
    )
    (net (code "52") (name "/LED35P") (class "Default")
      (node (ref "R38") (pin "2") (pinfunction "2_2") (pintype "passive"))
      (node (ref "U5") (pin "16") (pinfunction "O6_16") (pintype "passive"))
    )
    (net (code "53") (name "/LED36P") (class "Default")
      (node (ref "R39") (pin "2") (pinfunction "2_2") (pintype "passive"))
      (node (ref "U5") (pin "15") (pinfunction "O5_15") (pintype "passive"))
    )
    (net (code "54") (name "/LED37P") (class "Default")
      (node (ref "R40") (pin "2") (pinfunction "2_2") (pintype "passive"))
      (node (ref "U5") (pin "12") (pinfunction "O4_12") (pintype "passive"))
    )
    (net (code "55") (name "/LED40P") (class "Default")
      (node (ref "R41") (pin "2") (pinfunction "2_2") (pintype "passive"))
      (node (ref "U6") (pin "9") (pinfunction "O3_9") (pintype "passive"))
    )
    (net (code "56") (name "/LED41P") (class "Default")
      (node (ref "R42") (pin "2") (pinfunction "2_2") (pintype "passive"))
      (node (ref "U6") (pin "6") (pinfunction "O2_6") (pintype "passive"))
    )
    (net (code "57") (name "/LED42P") (class "Default")
      (node (ref "R43") (pin "2") (pinfunction "2_2") (pintype "passive"))
      (node (ref "U6") (pin "5") (pinfunction "O1_5") (pintype "passive"))
    )
    (net (code "58") (name "/LED43P") (class "Default")
      (node (ref "R44") (pin "2") (pinfunction "2_2") (pintype "passive"))
      (node (ref "U6") (pin "2") (pinfunction "O0_2") (pintype "passive"))
    )
    (net (code "59") (name "/LED44P") (class "Default")
      (node (ref "R45") (pin "2") (pinfunction "2_2") (pintype "passive"))
      (node (ref "U6") (pin "19") (pinfunction "O7_19") (pintype "passive"))
    )
    (net (code "60") (name "/LED45P") (class "Default")
      (node (ref "R46") (pin "2") (pinfunction "2_2") (pintype "passive"))
      (node (ref "U6") (pin "16") (pinfunction "O6_16") (pintype "passive"))
    )
    (net (code "61") (name "/LED46P") (class "Default")
      (node (ref "R47") (pin "2") (pinfunction "2_2") (pintype "passive"))
      (node (ref "U6") (pin "15") (pinfunction "O5_15") (pintype "passive"))
    )
    (net (code "62") (name "/LED47P") (class "Default")
      (node (ref "R48") (pin "2") (pinfunction "2_2") (pintype "passive"))
      (node (ref "U6") (pin "12") (pinfunction "O4_12") (pintype "passive"))
    )
    (net (code "63") (name "/LED50P") (class "Default")
      (node (ref "R49") (pin "2") (pinfunction "2_2") (pintype "passive"))
      (node (ref "U7") (pin "9") (pinfunction "O3_9") (pintype "passive"))
    )
    (net (code "64") (name "/LED51P") (class "Default")
      (node (ref "R50") (pin "2") (pinfunction "2_2") (pintype "passive"))
      (node (ref "U7") (pin "6") (pinfunction "O2_6") (pintype "passive"))
    )
    (net (code "65") (name "/LED52P") (class "Default")
      (node (ref "R51") (pin "2") (pinfunction "2_2") (pintype "passive"))
      (node (ref "U7") (pin "5") (pinfunction "O1_5") (pintype "passive"))
    )
    (net (code "66") (name "/LED53P") (class "Default")
      (node (ref "R52") (pin "2") (pinfunction "2_2") (pintype "passive"))
      (node (ref "U7") (pin "2") (pinfunction "O0_2") (pintype "passive"))
    )
    (net (code "67") (name "/LED54P") (class "Default")
      (node (ref "R53") (pin "2") (pinfunction "2_2") (pintype "passive"))
      (node (ref "U7") (pin "19") (pinfunction "O7_19") (pintype "passive"))
    )
    (net (code "68") (name "/LED55P") (class "Default")
      (node (ref "R54") (pin "2") (pinfunction "2_2") (pintype "passive"))
      (node (ref "U7") (pin "16") (pinfunction "O6_16") (pintype "passive"))
    )
    (net (code "69") (name "/LED56P") (class "Default")
      (node (ref "R55") (pin "2") (pinfunction "2_2") (pintype "passive"))
      (node (ref "U7") (pin "15") (pinfunction "O5_15") (pintype "passive"))
    )
    (net (code "70") (name "/LED57P") (class "Default")
      (node (ref "R56") (pin "2") (pinfunction "2_2") (pintype "passive"))
      (node (ref "U7") (pin "12") (pinfunction "O4_12") (pintype "passive"))
    )
    (net (code "71") (name "/LED60P") (class "Default")
      (node (ref "R57") (pin "2") (pinfunction "2_2") (pintype "passive"))
      (node (ref "U8") (pin "9") (pinfunction "O3_9") (pintype "passive"))
    )
    (net (code "72") (name "/LED61P") (class "Default")
      (node (ref "R58") (pin "2") (pinfunction "2_2") (pintype "passive"))
      (node (ref "U8") (pin "6") (pinfunction "O2_6") (pintype "passive"))
    )
    (net (code "73") (name "/LED62P") (class "Default")
      (node (ref "R59") (pin "2") (pinfunction "2_2") (pintype "passive"))
      (node (ref "U8") (pin "5") (pinfunction "O1_5") (pintype "passive"))
    )
    (net (code "74") (name "/LED63P") (class "Default")
      (node (ref "R60") (pin "2") (pinfunction "2_2") (pintype "passive"))
      (node (ref "U8") (pin "2") (pinfunction "O0_2") (pintype "passive"))
    )
    (net (code "75") (name "/LED64P") (class "Default")
      (node (ref "R61") (pin "2") (pinfunction "2_2") (pintype "passive"))
      (node (ref "U8") (pin "19") (pinfunction "O7_19") (pintype "passive"))
    )
    (net (code "76") (name "/LED65P") (class "Default")
      (node (ref "R62") (pin "2") (pinfunction "2_2") (pintype "passive"))
      (node (ref "U8") (pin "16") (pinfunction "O6_16") (pintype "passive"))
    )
    (net (code "77") (name "/LED66P") (class "Default")
      (node (ref "R63") (pin "2") (pinfunction "2_2") (pintype "passive"))
      (node (ref "U8") (pin "15") (pinfunction "O5_15") (pintype "passive"))
    )
    (net (code "78") (name "/LED67P") (class "Default")
      (node (ref "R64") (pin "2") (pinfunction "2_2") (pintype "passive"))
      (node (ref "U8") (pin "12") (pinfunction "O4_12") (pintype "passive"))
    )
    (net (code "79") (name "/LED70P") (class "Default")
      (node (ref "R65") (pin "2") (pinfunction "2_2") (pintype "passive"))
      (node (ref "U9") (pin "9") (pinfunction "O3_9") (pintype "passive"))
    )
    (net (code "80") (name "/LED71P") (class "Default")
      (node (ref "R66") (pin "2") (pinfunction "2_2") (pintype "passive"))
      (node (ref "U9") (pin "6") (pinfunction "O2_6") (pintype "passive"))
    )
    (net (code "81") (name "/LED72P") (class "Default")
      (node (ref "R67") (pin "2") (pinfunction "2_2") (pintype "passive"))
      (node (ref "U9") (pin "5") (pinfunction "O1_5") (pintype "passive"))
    )
    (net (code "82") (name "/LED73P") (class "Default")
      (node (ref "R68") (pin "2") (pinfunction "2_2") (pintype "passive"))
      (node (ref "U9") (pin "2") (pinfunction "O0_2") (pintype "passive"))
    )
    (net (code "83") (name "/LED74P") (class "Default")
      (node (ref "R69") (pin "2") (pinfunction "2_2") (pintype "passive"))
      (node (ref "U9") (pin "19") (pinfunction "O7_19") (pintype "passive"))
    )
    (net (code "84") (name "/LED75P") (class "Default")
      (node (ref "R70") (pin "2") (pinfunction "2_2") (pintype "passive"))
      (node (ref "U9") (pin "16") (pinfunction "O6_16") (pintype "passive"))
    )
    (net (code "85") (name "/LED76P") (class "Default")
      (node (ref "R71") (pin "2") (pinfunction "2_2") (pintype "passive"))
      (node (ref "U9") (pin "15") (pinfunction "O5_15") (pintype "passive"))
    )
    (net (code "86") (name "/LED77P") (class "Default")
      (node (ref "R72") (pin "2") (pinfunction "2_2") (pintype "passive"))
      (node (ref "U9") (pin "12") (pinfunction "O4_12") (pintype "passive"))
    )
    (net (code "87") (name "/ROW0C") (class "Default")
      (node (ref "R1") (pin "1") (pinfunction "1_1") (pintype "passive"))
      (node (ref "U10") (pin "2") (pinfunction "O0_2") (pintype "passive"))
    )
    (net (code "88") (name "/ROW0POW") (class "Default")
      (node (ref "H10") (pin "8") (pinfunction "8_8") (pintype "passive"))
      (node (ref "Q1") (pin "1") (pinfunction "C_1") (pintype "input"))
    )
    (net (code "89") (name "/ROW1C") (class "Default")
      (node (ref "R2") (pin "1") (pinfunction "1_1") (pintype "passive"))
      (node (ref "U10") (pin "5") (pinfunction "O1_5") (pintype "passive"))
    )
    (net (code "90") (name "/ROW1POW") (class "Default")
      (node (ref "H10") (pin "7") (pinfunction "7_7") (pintype "passive"))
      (node (ref "Q2") (pin "1") (pinfunction "C_1") (pintype "input"))
    )
    (net (code "91") (name "/ROW2C") (class "Default")
      (node (ref "R3") (pin "1") (pinfunction "1_1") (pintype "passive"))
      (node (ref "U10") (pin "6") (pinfunction "O2_6") (pintype "passive"))
    )
    (net (code "92") (name "/ROW2POW") (class "Default")
      (node (ref "H10") (pin "6") (pinfunction "6_6") (pintype "passive"))
      (node (ref "Q3") (pin "1") (pinfunction "C_1") (pintype "input"))
    )
    (net (code "93") (name "/ROW3C") (class "Default")
      (node (ref "R4") (pin "1") (pinfunction "1_1") (pintype "passive"))
      (node (ref "U10") (pin "9") (pinfunction "O3_9") (pintype "passive"))
    )
    (net (code "94") (name "/ROW3POW") (class "Default")
      (node (ref "H10") (pin "5") (pinfunction "5_5") (pintype "passive"))
      (node (ref "Q4") (pin "1") (pinfunction "C_1") (pintype "input"))
    )
    (net (code "95") (name "/ROW4C") (class "Default")
      (node (ref "R5") (pin "1") (pinfunction "1_1") (pintype "passive"))
      (node (ref "U10") (pin "19") (pinfunction "O7_19") (pintype "passive"))
    )
    (net (code "96") (name "/ROW4POW") (class "Default")
      (node (ref "H10") (pin "4") (pinfunction "4_4") (pintype "passive"))
      (node (ref "Q5") (pin "1") (pinfunction "C_1") (pintype "input"))
    )
    (net (code "97") (name "/ROW5C") (class "Default")
      (node (ref "R6") (pin "1") (pinfunction "1_1") (pintype "passive"))
      (node (ref "U10") (pin "16") (pinfunction "O6_16") (pintype "passive"))
    )
    (net (code "98") (name "/ROW5POW") (class "Default")
      (node (ref "H10") (pin "3") (pinfunction "3_3") (pintype "passive"))
      (node (ref "Q6") (pin "1") (pinfunction "C_1") (pintype "input"))
    )
    (net (code "99") (name "/ROW6C") (class "Default")
      (node (ref "R7") (pin "1") (pinfunction "1_1") (pintype "passive"))
      (node (ref "U10") (pin "15") (pinfunction "O5_15") (pintype "passive"))
    )
    (net (code "100") (name "/ROW6POW") (class "Default")
      (node (ref "H10") (pin "2") (pinfunction "2_2") (pintype "passive"))
      (node (ref "Q7") (pin "1") (pinfunction "C_1") (pintype "input"))
    )
    (net (code "101") (name "/ROW7C") (class "Default")
      (node (ref "R8") (pin "1") (pinfunction "1_1") (pintype "passive"))
      (node (ref "U10") (pin "12") (pinfunction "O4_12") (pintype "passive"))
    )
    (net (code "102") (name "/ROW7POW") (class "Default")
      (node (ref "H10") (pin "1") (pinfunction "1_1") (pintype "passive"))
      (node (ref "Q8") (pin "1") (pinfunction "C_1") (pintype "input"))
    )
    (net (code "103") (name "GND") (class "Default")
      (node (ref "C1") (pin "2") (pinfunction "2_2") (pintype "passive"))
      (node (ref "C10") (pin "1") (pinfunction "1_1") (pintype "passive"))
      (node (ref "C11") (pin "1") (pinfunction "1_1") (pintype "passive"))
      (node (ref "C12") (pin "1") (pinfunction "1_1") (pintype "passive"))
      (node (ref "C13") (pin "1") (pinfunction "1_1") (pintype "passive"))
      (node (ref "C14") (pin "1") (pinfunction "1_1") (pintype "passive"))
      (node (ref "C2") (pin "2") (pinfunction "2_2") (pintype "passive"))
      (node (ref "C3") (pin "2") (pinfunction "2_2") (pintype "passive"))
      (node (ref "C4") (pin "1") (pinfunction "1_1") (pintype "passive"))
      (node (ref "C5") (pin "1") (pinfunction "1_1") (pintype "passive"))
      (node (ref "C6") (pin "1") (pinfunction "1_1") (pintype "passive"))
      (node (ref "C7") (pin "1") (pinfunction "1_1") (pintype "passive"))
      (node (ref "C8") (pin "1") (pinfunction "1_1") (pintype "passive"))
      (node (ref "C9") (pin "1") (pinfunction "1_1") (pintype "passive"))
      (node (ref "H1") (pin "1") (pinfunction "1_1") (pintype "passive"))
      (node (ref "R74") (pin "1") (pinfunction "1_1") (pintype "passive"))
      (node (ref "SHEILD1") (pin "6") (pinfunction "GND_6") (pintype "passive"))
      (node (ref "SHEILD1") (pin "7") (pinfunction "GND_7") (pintype "passive"))
      (node (ref "U1") (pin "7") (pinfunction "Vee_7") (pintype "passive"))
      (node (ref "U1") (pin "8") (pinfunction "Vss_8") (pintype "passive"))
      (node (ref "U10") (pin "1") (pinfunction "EO_1") (pintype "passive"))
      (node (ref "U10") (pin "10") (pinfunction "Vss_10") (pintype "passive"))
      (node (ref "U2") (pin "1") (pinfunction "EO_1") (pintype "passive"))
      (node (ref "U2") (pin "10") (pinfunction "Vss_10") (pintype "passive"))
      (node (ref "U3") (pin "1") (pinfunction "EO_1") (pintype "passive"))
      (node (ref "U3") (pin "10") (pinfunction "Vss_10") (pintype "passive"))
      (node (ref "U4") (pin "1") (pinfunction "EO_1") (pintype "passive"))
      (node (ref "U4") (pin "10") (pinfunction "Vss_10") (pintype "passive"))
      (node (ref "U5") (pin "1") (pinfunction "EO_1") (pintype "passive"))
      (node (ref "U5") (pin "10") (pinfunction "Vss_10") (pintype "passive"))
      (node (ref "U6") (pin "1") (pinfunction "EO_1") (pintype "passive"))
      (node (ref "U6") (pin "10") (pinfunction "Vss_10") (pintype "passive"))
      (node (ref "U7") (pin "1") (pinfunction "EO_1") (pintype "passive"))
      (node (ref "U7") (pin "10") (pinfunction "Vss_10") (pintype "passive"))
      (node (ref "U8") (pin "1") (pinfunction "EO_1") (pintype "passive"))
      (node (ref "U8") (pin "10") (pinfunction "Vss_10") (pintype "passive"))
      (node (ref "U9") (pin "1") (pinfunction "EO_1") (pintype "passive"))
      (node (ref "U9") (pin "10") (pinfunction "Vss_10") (pintype "passive"))
    )
    (net (code "104") (name "Net-(H2-Pad1)") (class "Default")
      (node (ref "H2") (pin "1") (pinfunction "1_1") (pintype "passive"))
      (node (ref "R9") (pin "1") (pinfunction "1_1") (pintype "passive"))
    )
    (net (code "105") (name "Net-(H2-Pad2)") (class "Default")
      (node (ref "H2") (pin "2") (pinfunction "2_2") (pintype "passive"))
      (node (ref "R10") (pin "1") (pinfunction "1_1") (pintype "passive"))
    )
    (net (code "106") (name "Net-(H2-Pad3)") (class "Default")
      (node (ref "H2") (pin "3") (pinfunction "3_3") (pintype "passive"))
      (node (ref "R11") (pin "1") (pinfunction "1_1") (pintype "passive"))
    )
    (net (code "107") (name "Net-(H2-Pad4)") (class "Default")
      (node (ref "H2") (pin "4") (pinfunction "4_4") (pintype "passive"))
      (node (ref "R12") (pin "1") (pinfunction "1_1") (pintype "passive"))
    )
    (net (code "108") (name "Net-(H2-Pad5)") (class "Default")
      (node (ref "H2") (pin "5") (pinfunction "5_5") (pintype "passive"))
      (node (ref "R13") (pin "1") (pinfunction "1_1") (pintype "passive"))
    )
    (net (code "109") (name "Net-(H2-Pad6)") (class "Default")
      (node (ref "H2") (pin "6") (pinfunction "6_6") (pintype "passive"))
      (node (ref "R14") (pin "1") (pinfunction "1_1") (pintype "passive"))
    )
    (net (code "110") (name "Net-(H2-Pad7)") (class "Default")
      (node (ref "H2") (pin "7") (pinfunction "7_7") (pintype "passive"))
      (node (ref "R15") (pin "1") (pinfunction "1_1") (pintype "passive"))
    )
    (net (code "111") (name "Net-(H2-Pad8)") (class "Default")
      (node (ref "H2") (pin "8") (pinfunction "8_8") (pintype "passive"))
      (node (ref "R16") (pin "1") (pinfunction "1_1") (pintype "passive"))
    )
    (net (code "112") (name "Net-(H3-Pad1)") (class "Default")
      (node (ref "H3") (pin "1") (pinfunction "1_1") (pintype "passive"))
      (node (ref "R17") (pin "1") (pinfunction "1_1") (pintype "passive"))
    )
    (net (code "113") (name "Net-(H3-Pad2)") (class "Default")
      (node (ref "H3") (pin "2") (pinfunction "2_2") (pintype "passive"))
      (node (ref "R18") (pin "1") (pinfunction "1_1") (pintype "passive"))
    )
    (net (code "114") (name "Net-(H3-Pad3)") (class "Default")
      (node (ref "H3") (pin "3") (pinfunction "3_3") (pintype "passive"))
      (node (ref "R19") (pin "1") (pinfunction "1_1") (pintype "passive"))
    )
    (net (code "115") (name "Net-(H3-Pad4)") (class "Default")
      (node (ref "H3") (pin "4") (pinfunction "4_4") (pintype "passive"))
      (node (ref "R20") (pin "1") (pinfunction "1_1") (pintype "passive"))
    )
    (net (code "116") (name "Net-(H3-Pad5)") (class "Default")
      (node (ref "H3") (pin "5") (pinfunction "5_5") (pintype "passive"))
      (node (ref "R21") (pin "1") (pinfunction "1_1") (pintype "passive"))
    )
    (net (code "117") (name "Net-(H3-Pad6)") (class "Default")
      (node (ref "H3") (pin "6") (pinfunction "6_6") (pintype "passive"))
      (node (ref "R22") (pin "1") (pinfunction "1_1") (pintype "passive"))
    )
    (net (code "118") (name "Net-(H3-Pad7)") (class "Default")
      (node (ref "H3") (pin "7") (pinfunction "7_7") (pintype "passive"))
      (node (ref "R23") (pin "1") (pinfunction "1_1") (pintype "passive"))
    )
    (net (code "119") (name "Net-(H3-Pad8)") (class "Default")
      (node (ref "H3") (pin "8") (pinfunction "8_8") (pintype "passive"))
      (node (ref "R24") (pin "1") (pinfunction "1_1") (pintype "passive"))
    )
    (net (code "120") (name "Net-(H4-Pad1)") (class "Default")
      (node (ref "H4") (pin "1") (pinfunction "1_1") (pintype "passive"))
      (node (ref "R25") (pin "1") (pinfunction "1_1") (pintype "passive"))
    )
    (net (code "121") (name "Net-(H4-Pad2)") (class "Default")
      (node (ref "H4") (pin "2") (pinfunction "2_2") (pintype "passive"))
      (node (ref "R26") (pin "1") (pinfunction "1_1") (pintype "passive"))
    )
    (net (code "122") (name "Net-(H4-Pad3)") (class "Default")
      (node (ref "H4") (pin "3") (pinfunction "3_3") (pintype "passive"))
      (node (ref "R27") (pin "1") (pinfunction "1_1") (pintype "passive"))
    )
    (net (code "123") (name "Net-(H4-Pad4)") (class "Default")
      (node (ref "H4") (pin "4") (pinfunction "4_4") (pintype "passive"))
      (node (ref "R28") (pin "1") (pinfunction "1_1") (pintype "passive"))
    )
    (net (code "124") (name "Net-(H4-Pad5)") (class "Default")
      (node (ref "H4") (pin "5") (pinfunction "5_5") (pintype "passive"))
      (node (ref "R29") (pin "1") (pinfunction "1_1") (pintype "passive"))
    )
    (net (code "125") (name "Net-(H4-Pad6)") (class "Default")
      (node (ref "H4") (pin "6") (pinfunction "6_6") (pintype "passive"))
      (node (ref "R30") (pin "1") (pinfunction "1_1") (pintype "passive"))
    )
    (net (code "126") (name "Net-(H4-Pad7)") (class "Default")
      (node (ref "H4") (pin "7") (pinfunction "7_7") (pintype "passive"))
      (node (ref "R31") (pin "1") (pinfunction "1_1") (pintype "passive"))
    )
    (net (code "127") (name "Net-(H4-Pad8)") (class "Default")
      (node (ref "H4") (pin "8") (pinfunction "8_8") (pintype "passive"))
      (node (ref "R32") (pin "1") (pinfunction "1_1") (pintype "passive"))
    )
    (net (code "128") (name "Net-(H5-Pad1)") (class "Default")
      (node (ref "H5") (pin "1") (pinfunction "1_1") (pintype "passive"))
      (node (ref "R33") (pin "1") (pinfunction "1_1") (pintype "passive"))
    )
    (net (code "129") (name "Net-(H5-Pad2)") (class "Default")
      (node (ref "H5") (pin "2") (pinfunction "2_2") (pintype "passive"))
      (node (ref "R34") (pin "1") (pinfunction "1_1") (pintype "passive"))
    )
    (net (code "130") (name "Net-(H5-Pad3)") (class "Default")
      (node (ref "H5") (pin "3") (pinfunction "3_3") (pintype "passive"))
      (node (ref "R35") (pin "1") (pinfunction "1_1") (pintype "passive"))
    )
    (net (code "131") (name "Net-(H5-Pad4)") (class "Default")
      (node (ref "H5") (pin "4") (pinfunction "4_4") (pintype "passive"))
      (node (ref "R36") (pin "1") (pinfunction "1_1") (pintype "passive"))
    )
    (net (code "132") (name "Net-(H5-Pad5)") (class "Default")
      (node (ref "H5") (pin "5") (pinfunction "5_5") (pintype "passive"))
      (node (ref "R37") (pin "1") (pinfunction "1_1") (pintype "passive"))
    )
    (net (code "133") (name "Net-(H5-Pad6)") (class "Default")
      (node (ref "H5") (pin "6") (pinfunction "6_6") (pintype "passive"))
      (node (ref "R38") (pin "1") (pinfunction "1_1") (pintype "passive"))
    )
    (net (code "134") (name "Net-(H5-Pad7)") (class "Default")
      (node (ref "H5") (pin "7") (pinfunction "7_7") (pintype "passive"))
      (node (ref "R39") (pin "1") (pinfunction "1_1") (pintype "passive"))
    )
    (net (code "135") (name "Net-(H5-Pad8)") (class "Default")
      (node (ref "H5") (pin "8") (pinfunction "8_8") (pintype "passive"))
      (node (ref "R40") (pin "1") (pinfunction "1_1") (pintype "passive"))
    )
    (net (code "136") (name "Net-(H6-Pad1)") (class "Default")
      (node (ref "H6") (pin "1") (pinfunction "1_1") (pintype "passive"))
      (node (ref "R41") (pin "1") (pinfunction "1_1") (pintype "passive"))
    )
    (net (code "137") (name "Net-(H6-Pad2)") (class "Default")
      (node (ref "H6") (pin "2") (pinfunction "2_2") (pintype "passive"))
      (node (ref "R42") (pin "1") (pinfunction "1_1") (pintype "passive"))
    )
    (net (code "138") (name "Net-(H6-Pad3)") (class "Default")
      (node (ref "H6") (pin "3") (pinfunction "3_3") (pintype "passive"))
      (node (ref "R43") (pin "1") (pinfunction "1_1") (pintype "passive"))
    )
    (net (code "139") (name "Net-(H6-Pad4)") (class "Default")
      (node (ref "H6") (pin "4") (pinfunction "4_4") (pintype "passive"))
      (node (ref "R44") (pin "1") (pinfunction "1_1") (pintype "passive"))
    )
    (net (code "140") (name "Net-(H6-Pad5)") (class "Default")
      (node (ref "H6") (pin "5") (pinfunction "5_5") (pintype "passive"))
      (node (ref "R45") (pin "1") (pinfunction "1_1") (pintype "passive"))
    )
    (net (code "141") (name "Net-(H6-Pad6)") (class "Default")
      (node (ref "H6") (pin "6") (pinfunction "6_6") (pintype "passive"))
      (node (ref "R46") (pin "1") (pinfunction "1_1") (pintype "passive"))
    )
    (net (code "142") (name "Net-(H6-Pad7)") (class "Default")
      (node (ref "H6") (pin "7") (pinfunction "7_7") (pintype "passive"))
      (node (ref "R47") (pin "1") (pinfunction "1_1") (pintype "passive"))
    )
    (net (code "143") (name "Net-(H6-Pad8)") (class "Default")
      (node (ref "H6") (pin "8") (pinfunction "8_8") (pintype "passive"))
      (node (ref "R48") (pin "1") (pinfunction "1_1") (pintype "passive"))
    )
    (net (code "144") (name "Net-(H7-Pad1)") (class "Default")
      (node (ref "H7") (pin "1") (pinfunction "1_1") (pintype "passive"))
      (node (ref "R49") (pin "1") (pinfunction "1_1") (pintype "passive"))
    )
    (net (code "145") (name "Net-(H7-Pad2)") (class "Default")
      (node (ref "H7") (pin "2") (pinfunction "2_2") (pintype "passive"))
      (node (ref "R50") (pin "1") (pinfunction "1_1") (pintype "passive"))
    )
    (net (code "146") (name "Net-(H7-Pad3)") (class "Default")
      (node (ref "H7") (pin "3") (pinfunction "3_3") (pintype "passive"))
      (node (ref "R51") (pin "1") (pinfunction "1_1") (pintype "passive"))
    )
    (net (code "147") (name "Net-(H7-Pad4)") (class "Default")
      (node (ref "H7") (pin "4") (pinfunction "4_4") (pintype "passive"))
      (node (ref "R52") (pin "1") (pinfunction "1_1") (pintype "passive"))
    )
    (net (code "148") (name "Net-(H7-Pad5)") (class "Default")
      (node (ref "H7") (pin "5") (pinfunction "5_5") (pintype "passive"))
      (node (ref "R53") (pin "1") (pinfunction "1_1") (pintype "passive"))
    )
    (net (code "149") (name "Net-(H7-Pad6)") (class "Default")
      (node (ref "H7") (pin "6") (pinfunction "6_6") (pintype "passive"))
      (node (ref "R54") (pin "1") (pinfunction "1_1") (pintype "passive"))
    )
    (net (code "150") (name "Net-(H7-Pad7)") (class "Default")
      (node (ref "H7") (pin "7") (pinfunction "7_7") (pintype "passive"))
      (node (ref "R55") (pin "1") (pinfunction "1_1") (pintype "passive"))
    )
    (net (code "151") (name "Net-(H7-Pad8)") (class "Default")
      (node (ref "H7") (pin "8") (pinfunction "8_8") (pintype "passive"))
      (node (ref "R56") (pin "1") (pinfunction "1_1") (pintype "passive"))
    )
    (net (code "152") (name "Net-(H8-Pad1)") (class "Default")
      (node (ref "H8") (pin "1") (pinfunction "1_1") (pintype "passive"))
      (node (ref "R57") (pin "1") (pinfunction "1_1") (pintype "passive"))
    )
    (net (code "153") (name "Net-(H8-Pad2)") (class "Default")
      (node (ref "H8") (pin "2") (pinfunction "2_2") (pintype "passive"))
      (node (ref "R58") (pin "1") (pinfunction "1_1") (pintype "passive"))
    )
    (net (code "154") (name "Net-(H8-Pad3)") (class "Default")
      (node (ref "H8") (pin "3") (pinfunction "3_3") (pintype "passive"))
      (node (ref "R59") (pin "1") (pinfunction "1_1") (pintype "passive"))
    )
    (net (code "155") (name "Net-(H8-Pad4)") (class "Default")
      (node (ref "H8") (pin "4") (pinfunction "4_4") (pintype "passive"))
      (node (ref "R60") (pin "1") (pinfunction "1_1") (pintype "passive"))
    )
    (net (code "156") (name "Net-(H8-Pad5)") (class "Default")
      (node (ref "H8") (pin "5") (pinfunction "5_5") (pintype "passive"))
      (node (ref "R61") (pin "1") (pinfunction "1_1") (pintype "passive"))
    )
    (net (code "157") (name "Net-(H8-Pad6)") (class "Default")
      (node (ref "H8") (pin "6") (pinfunction "6_6") (pintype "passive"))
      (node (ref "R62") (pin "1") (pinfunction "1_1") (pintype "passive"))
    )
    (net (code "158") (name "Net-(H8-Pad7)") (class "Default")
      (node (ref "H8") (pin "7") (pinfunction "7_7") (pintype "passive"))
      (node (ref "R63") (pin "1") (pinfunction "1_1") (pintype "passive"))
    )
    (net (code "159") (name "Net-(H8-Pad8)") (class "Default")
      (node (ref "H8") (pin "8") (pinfunction "8_8") (pintype "passive"))
      (node (ref "R64") (pin "1") (pinfunction "1_1") (pintype "passive"))
    )
    (net (code "160") (name "Net-(H9-Pad1)") (class "Default")
      (node (ref "H9") (pin "1") (pinfunction "1_1") (pintype "passive"))
      (node (ref "R65") (pin "1") (pinfunction "1_1") (pintype "passive"))
    )
    (net (code "161") (name "Net-(H9-Pad2)") (class "Default")
      (node (ref "H9") (pin "2") (pinfunction "2_2") (pintype "passive"))
      (node (ref "R66") (pin "1") (pinfunction "1_1") (pintype "passive"))
    )
    (net (code "162") (name "Net-(H9-Pad3)") (class "Default")
      (node (ref "H9") (pin "3") (pinfunction "3_3") (pintype "passive"))
      (node (ref "R67") (pin "1") (pinfunction "1_1") (pintype "passive"))
    )
    (net (code "163") (name "Net-(H9-Pad4)") (class "Default")
      (node (ref "H9") (pin "4") (pinfunction "4_4") (pintype "passive"))
      (node (ref "R68") (pin "1") (pinfunction "1_1") (pintype "passive"))
    )
    (net (code "164") (name "Net-(H9-Pad5)") (class "Default")
      (node (ref "H9") (pin "5") (pinfunction "5_5") (pintype "passive"))
      (node (ref "R69") (pin "1") (pinfunction "1_1") (pintype "passive"))
    )
    (net (code "165") (name "Net-(H9-Pad6)") (class "Default")
      (node (ref "H9") (pin "6") (pinfunction "6_6") (pintype "passive"))
      (node (ref "R70") (pin "1") (pinfunction "1_1") (pintype "passive"))
    )
    (net (code "166") (name "Net-(H9-Pad7)") (class "Default")
      (node (ref "H9") (pin "7") (pinfunction "7_7") (pintype "passive"))
      (node (ref "R71") (pin "1") (pinfunction "1_1") (pintype "passive"))
    )
    (net (code "167") (name "Net-(H9-Pad8)") (class "Default")
      (node (ref "H9") (pin "8") (pinfunction "8_8") (pintype "passive"))
      (node (ref "R72") (pin "1") (pinfunction "1_1") (pintype "passive"))
    )
    (net (code "168") (name "Net-(Q1-B)") (class "Default")
      (node (ref "Q1") (pin "2") (pinfunction "B_2") (pintype "input"))
      (node (ref "R1") (pin "2") (pinfunction "2_2") (pintype "passive"))
    )
    (net (code "169") (name "Net-(Q2-B)") (class "Default")
      (node (ref "Q2") (pin "2") (pinfunction "B_2") (pintype "input"))
      (node (ref "R2") (pin "2") (pinfunction "2_2") (pintype "passive"))
    )
    (net (code "170") (name "Net-(Q3-B)") (class "Default")
      (node (ref "Q3") (pin "2") (pinfunction "B_2") (pintype "input"))
      (node (ref "R3") (pin "2") (pinfunction "2_2") (pintype "passive"))
    )
    (net (code "171") (name "Net-(Q4-B)") (class "Default")
      (node (ref "Q4") (pin "2") (pinfunction "B_2") (pintype "input"))
      (node (ref "R4") (pin "2") (pinfunction "2_2") (pintype "passive"))
    )
    (net (code "172") (name "Net-(Q5-B)") (class "Default")
      (node (ref "Q5") (pin "2") (pinfunction "B_2") (pintype "input"))
      (node (ref "R5") (pin "2") (pinfunction "2_2") (pintype "passive"))
    )
    (net (code "173") (name "Net-(Q6-B)") (class "Default")
      (node (ref "Q6") (pin "2") (pinfunction "B_2") (pintype "input"))
      (node (ref "R6") (pin "2") (pinfunction "2_2") (pintype "passive"))
    )
    (net (code "174") (name "Net-(Q7-B)") (class "Default")
      (node (ref "Q7") (pin "2") (pinfunction "B_2") (pintype "input"))
      (node (ref "R7") (pin "2") (pinfunction "2_2") (pintype "passive"))
    )
    (net (code "175") (name "Net-(Q8-B)") (class "Default")
      (node (ref "Q8") (pin "2") (pinfunction "B_2") (pintype "input"))
      (node (ref "R8") (pin "2") (pinfunction "2_2") (pintype "passive"))
    )
    (net (code "176") (name "VCC") (class "Default")
      (node (ref "C1") (pin "1") (pinfunction "1_1") (pintype "passive"))
      (node (ref "C10") (pin "2") (pinfunction "2_2") (pintype "passive"))
      (node (ref "C11") (pin "2") (pinfunction "2_2") (pintype "passive"))
      (node (ref "C12") (pin "2") (pinfunction "2_2") (pintype "passive"))
      (node (ref "C13") (pin "2") (pinfunction "2_2") (pintype "passive"))
      (node (ref "C14") (pin "2") (pinfunction "2_2") (pintype "passive"))
      (node (ref "C2") (pin "1") (pinfunction "1_1") (pintype "passive"))
      (node (ref "C3") (pin "1") (pinfunction "1_1") (pintype "passive"))
      (node (ref "C4") (pin "2") (pinfunction "2_2") (pintype "passive"))
      (node (ref "C5") (pin "2") (pinfunction "2_2") (pintype "passive"))
      (node (ref "C6") (pin "2") (pinfunction "2_2") (pintype "passive"))
      (node (ref "C7") (pin "2") (pinfunction "2_2") (pintype "passive"))
      (node (ref "C8") (pin "2") (pinfunction "2_2") (pintype "passive"))
      (node (ref "C9") (pin "2") (pinfunction "2_2") (pintype "passive"))
      (node (ref "H1") (pin "2") (pinfunction "2_2") (pintype "passive"))
      (node (ref "Q1") (pin "3") (pinfunction "E_3") (pintype "input"))
      (node (ref "Q2") (pin "3") (pinfunction "E_3") (pintype "input"))
      (node (ref "Q3") (pin "3") (pinfunction "E_3") (pintype "input"))
      (node (ref "Q4") (pin "3") (pinfunction "E_3") (pintype "input"))
      (node (ref "Q5") (pin "3") (pinfunction "E_3") (pintype "input"))
      (node (ref "Q6") (pin "3") (pinfunction "E_3") (pintype "input"))
      (node (ref "Q7") (pin "3") (pinfunction "E_3") (pintype "input"))
      (node (ref "Q8") (pin "3") (pinfunction "E_3") (pintype "input"))
      (node (ref "R73") (pin "2") (pinfunction "2_2") (pintype "passive"))
      (node (ref "SHEILD1") (pin "5") (pinfunction "5V_5") (pintype "passive"))
      (node (ref "U1") (pin "16") (pinfunction "Vdd_16") (pintype "passive"))
      (node (ref "U10") (pin "20") (pinfunction "Vdd_20") (pintype "passive"))
      (node (ref "U2") (pin "20") (pinfunction "Vdd_20") (pintype "passive"))
      (node (ref "U3") (pin "20") (pinfunction "Vdd_20") (pintype "passive"))
      (node (ref "U4") (pin "20") (pinfunction "Vdd_20") (pintype "passive"))
      (node (ref "U5") (pin "20") (pinfunction "Vdd_20") (pintype "passive"))
      (node (ref "U6") (pin "20") (pinfunction "Vdd_20") (pintype "passive"))
      (node (ref "U7") (pin "20") (pinfunction "Vdd_20") (pintype "passive"))
      (node (ref "U8") (pin "20") (pinfunction "Vdd_20") (pintype "passive"))
      (node (ref "U9") (pin "20") (pinfunction "Vdd_20") (pintype "passive"))
    )
    (net (code "177") (name "unconnected-(SHEILD1-0-Pad15)") (class "Default")
      (node (ref "SHEILD1") (pin "15") (pinfunction "0_15") (pintype "passive"))
    )
    (net (code "178") (name "unconnected-(SHEILD1-1-Pad16)") (class "Default")
      (node (ref "SHEILD1") (pin "16") (pinfunction "1_16") (pintype "passive"))
    )
    (net (code "179") (name "unconnected-(SHEILD1-3V3-Pad4)") (class "Default")
      (node (ref "SHEILD1") (pin "4") (pinfunction "3V3_4") (pintype "passive"))
    )
    (net (code "180") (name "unconnected-(SHEILD1-5V-Pad37)") (class "Default")
      (node (ref "SHEILD1") (pin "37") (pinfunction "5V_37") (pintype "passive"))
    )
    (net (code "181") (name "unconnected-(SHEILD1-A1-Pad10)") (class "Default")
      (node (ref "SHEILD1") (pin "10") (pinfunction "A1_10") (pintype "passive"))
    )
    (net (code "182") (name "unconnected-(SHEILD1-A2-Pad11)") (class "Default")
      (node (ref "SHEILD1") (pin "11") (pinfunction "A2_11") (pintype "passive"))
    )
    (net (code "183") (name "unconnected-(SHEILD1-A3-Pad12)") (class "Default")
      (node (ref "SHEILD1") (pin "12") (pinfunction "A3_12") (pintype "passive"))
    )
    (net (code "184") (name "unconnected-(SHEILD1-A4-Pad13)") (class "Default")
      (node (ref "SHEILD1") (pin "13") (pinfunction "A4_13") (pintype "passive"))
    )
    (net (code "185") (name "unconnected-(SHEILD1-AREF-Pad30)") (class "Default")
      (node (ref "SHEILD1") (pin "30") (pinfunction "AREF_30") (pintype "passive"))
    )
    (net (code "186") (name "unconnected-(SHEILD1-GND-Pad29)") (class "Default")
      (node (ref "SHEILD1") (pin "29") (pinfunction "GND_29") (pintype "passive"))
    )
    (net (code "187") (name "unconnected-(SHEILD1-GND-Pad34)") (class "Default")
      (node (ref "SHEILD1") (pin "34") (pinfunction "GND_34") (pintype "passive"))
    )
    (net (code "188") (name "unconnected-(SHEILD1-IO{slash}REF-Pad2)") (class "Default")
      (node (ref "SHEILD1") (pin "2") (pinfunction "IO/REF_2") (pintype "passive"))
    )
    (net (code "189") (name "unconnected-(SHEILD1-MISO-Pad38)") (class "Default")
      (node (ref "SHEILD1") (pin "38") (pinfunction "MISO_38") (pintype "passive"))
    )
    (net (code "190") (name "unconnected-(SHEILD1-MOSI-Pad36)") (class "Default")
      (node (ref "SHEILD1") (pin "36") (pinfunction "MOSI_36") (pintype "passive"))
    )
    (net (code "191") (name "unconnected-(SHEILD1-Pad1)") (class "Default")
      (node (ref "SHEILD1") (pin "1") (pintype "passive"))
    )
    (net (code "192") (name "unconnected-(SHEILD1-RESET-Pad3)") (class "Default")
      (node (ref "SHEILD1") (pin "3") (pinfunction "RESET_3") (pintype "passive"))
    )
    (net (code "193") (name "unconnected-(SHEILD1-RESET-Pad33)") (class "Default")
      (node (ref "SHEILD1") (pin "33") (pinfunction "RESET_33") (pintype "passive"))
    )
    (net (code "194") (name "unconnected-(SHEILD1-SCK-Pad35)") (class "Default")
      (node (ref "SHEILD1") (pin "35") (pinfunction "SCK_35") (pintype "passive"))
    )
    (net (code "195") (name "unconnected-(SHEILD1-SCL-Pad32)") (class "Default")
      (node (ref "SHEILD1") (pin "32") (pinfunction "SCL_32") (pintype "passive"))
    )
    (net (code "196") (name "unconnected-(SHEILD1-SDA-Pad31)") (class "Default")
      (node (ref "SHEILD1") (pin "31") (pinfunction "SDA_31") (pintype "passive"))
    )
    (net (code "197") (name "unconnected-(SHEILD1-VIN-Pad8)") (class "Default")
      (node (ref "SHEILD1") (pin "8") (pinfunction "VIN_8") (pintype "passive"))
    )
  )
)
